# NutX_Keyboard_PCB_ANSI104.net
KiCad netlist of a schematic drawn in Altium Designer
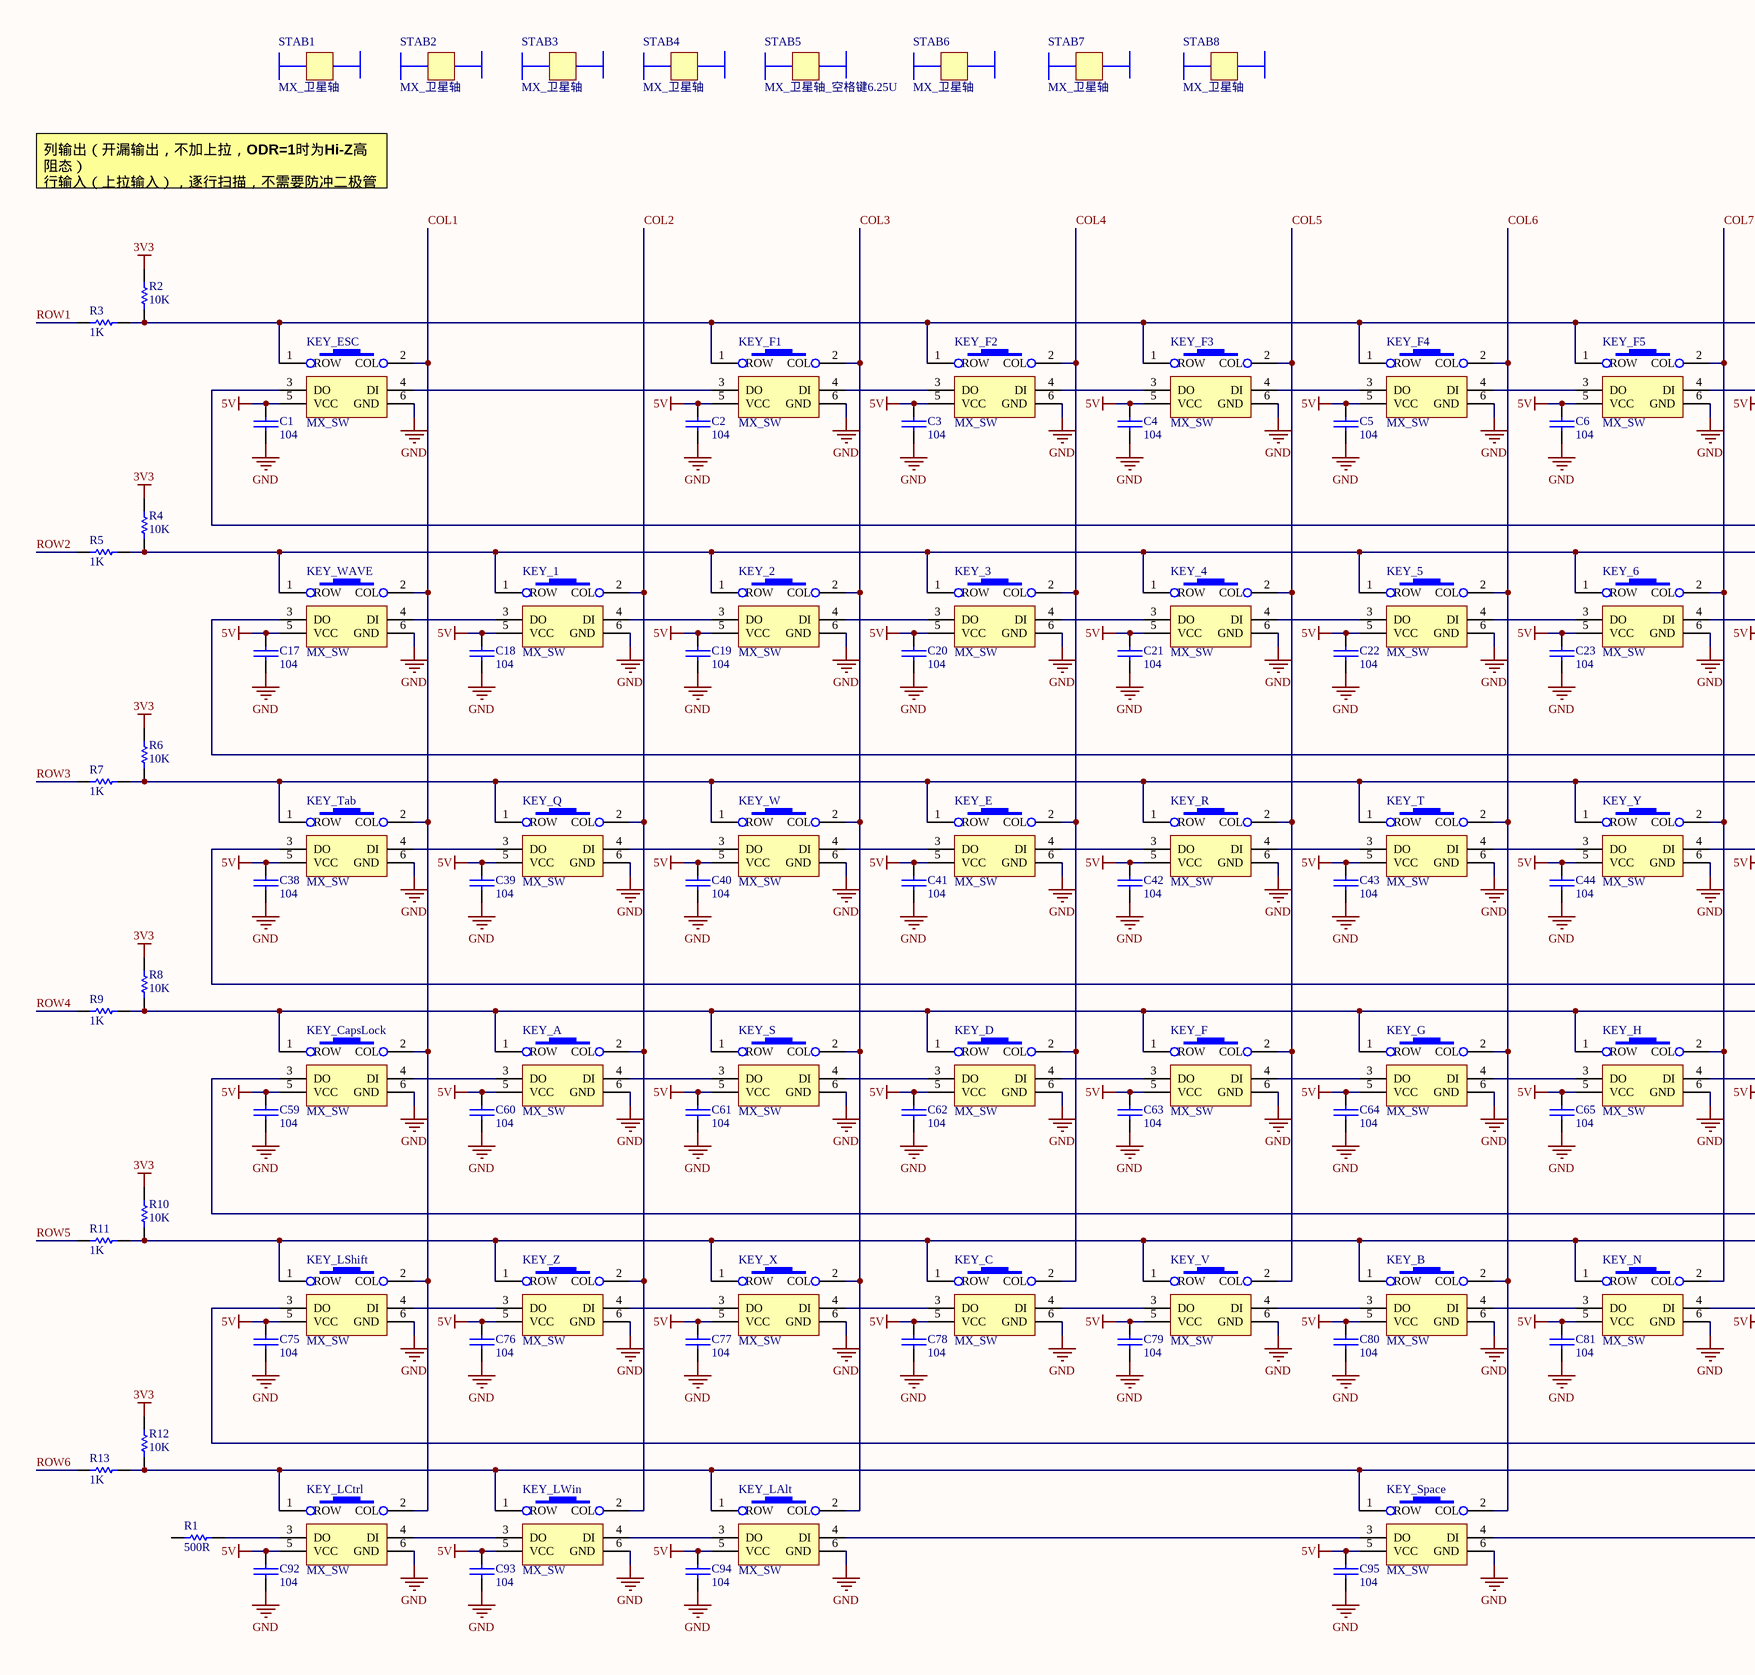
[diagram p0: NutX_Keyboard_PCB_ANSI104.SchDoc, left]
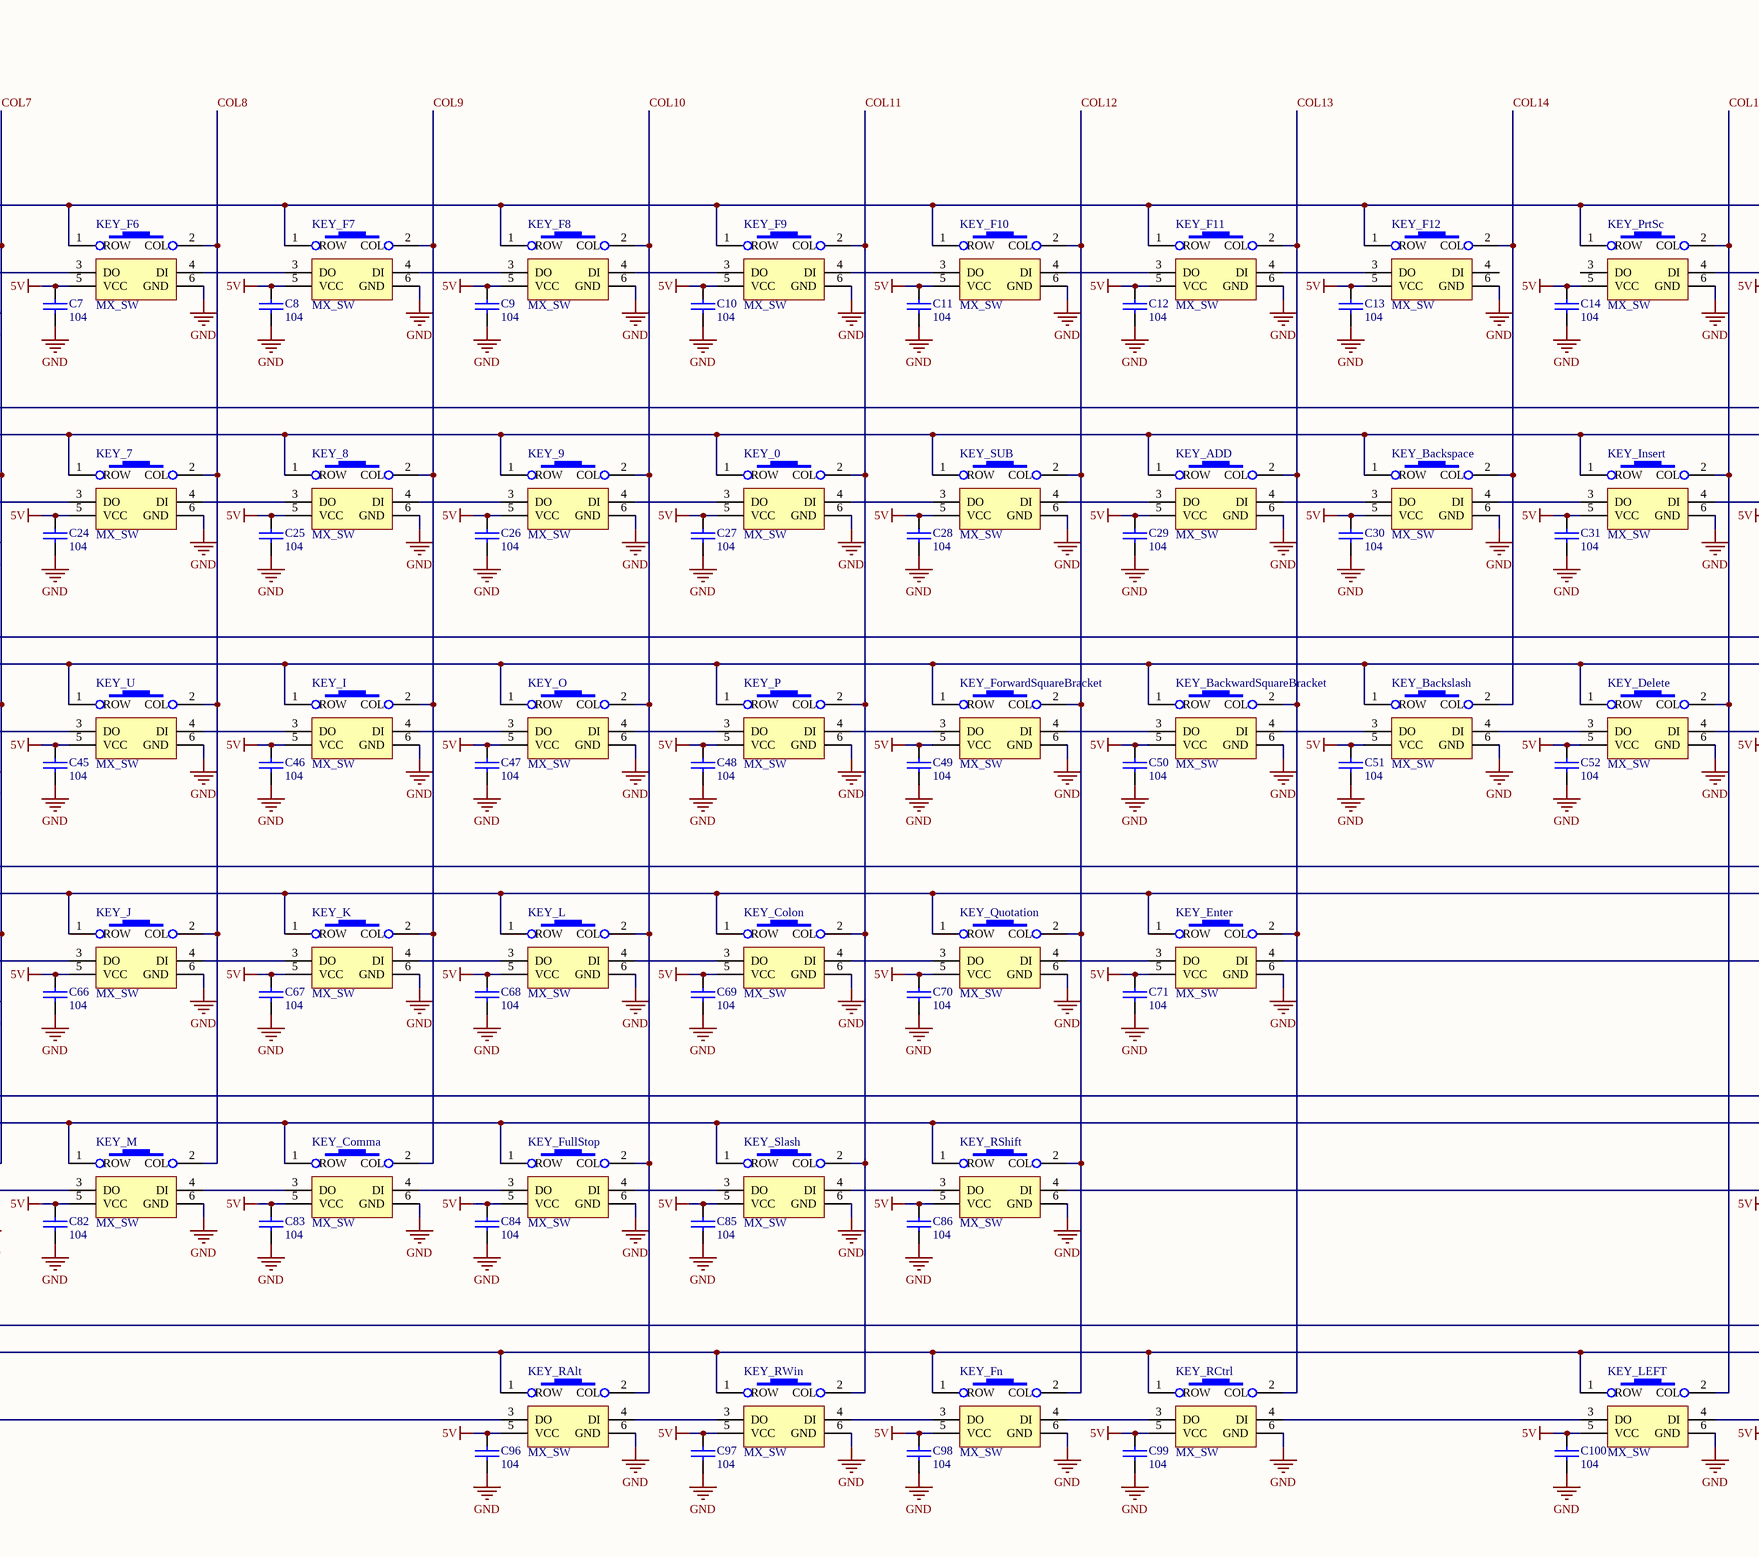
[diagram p1: NutX_Keyboard_PCB_ANSI104.SchDoc, middle]
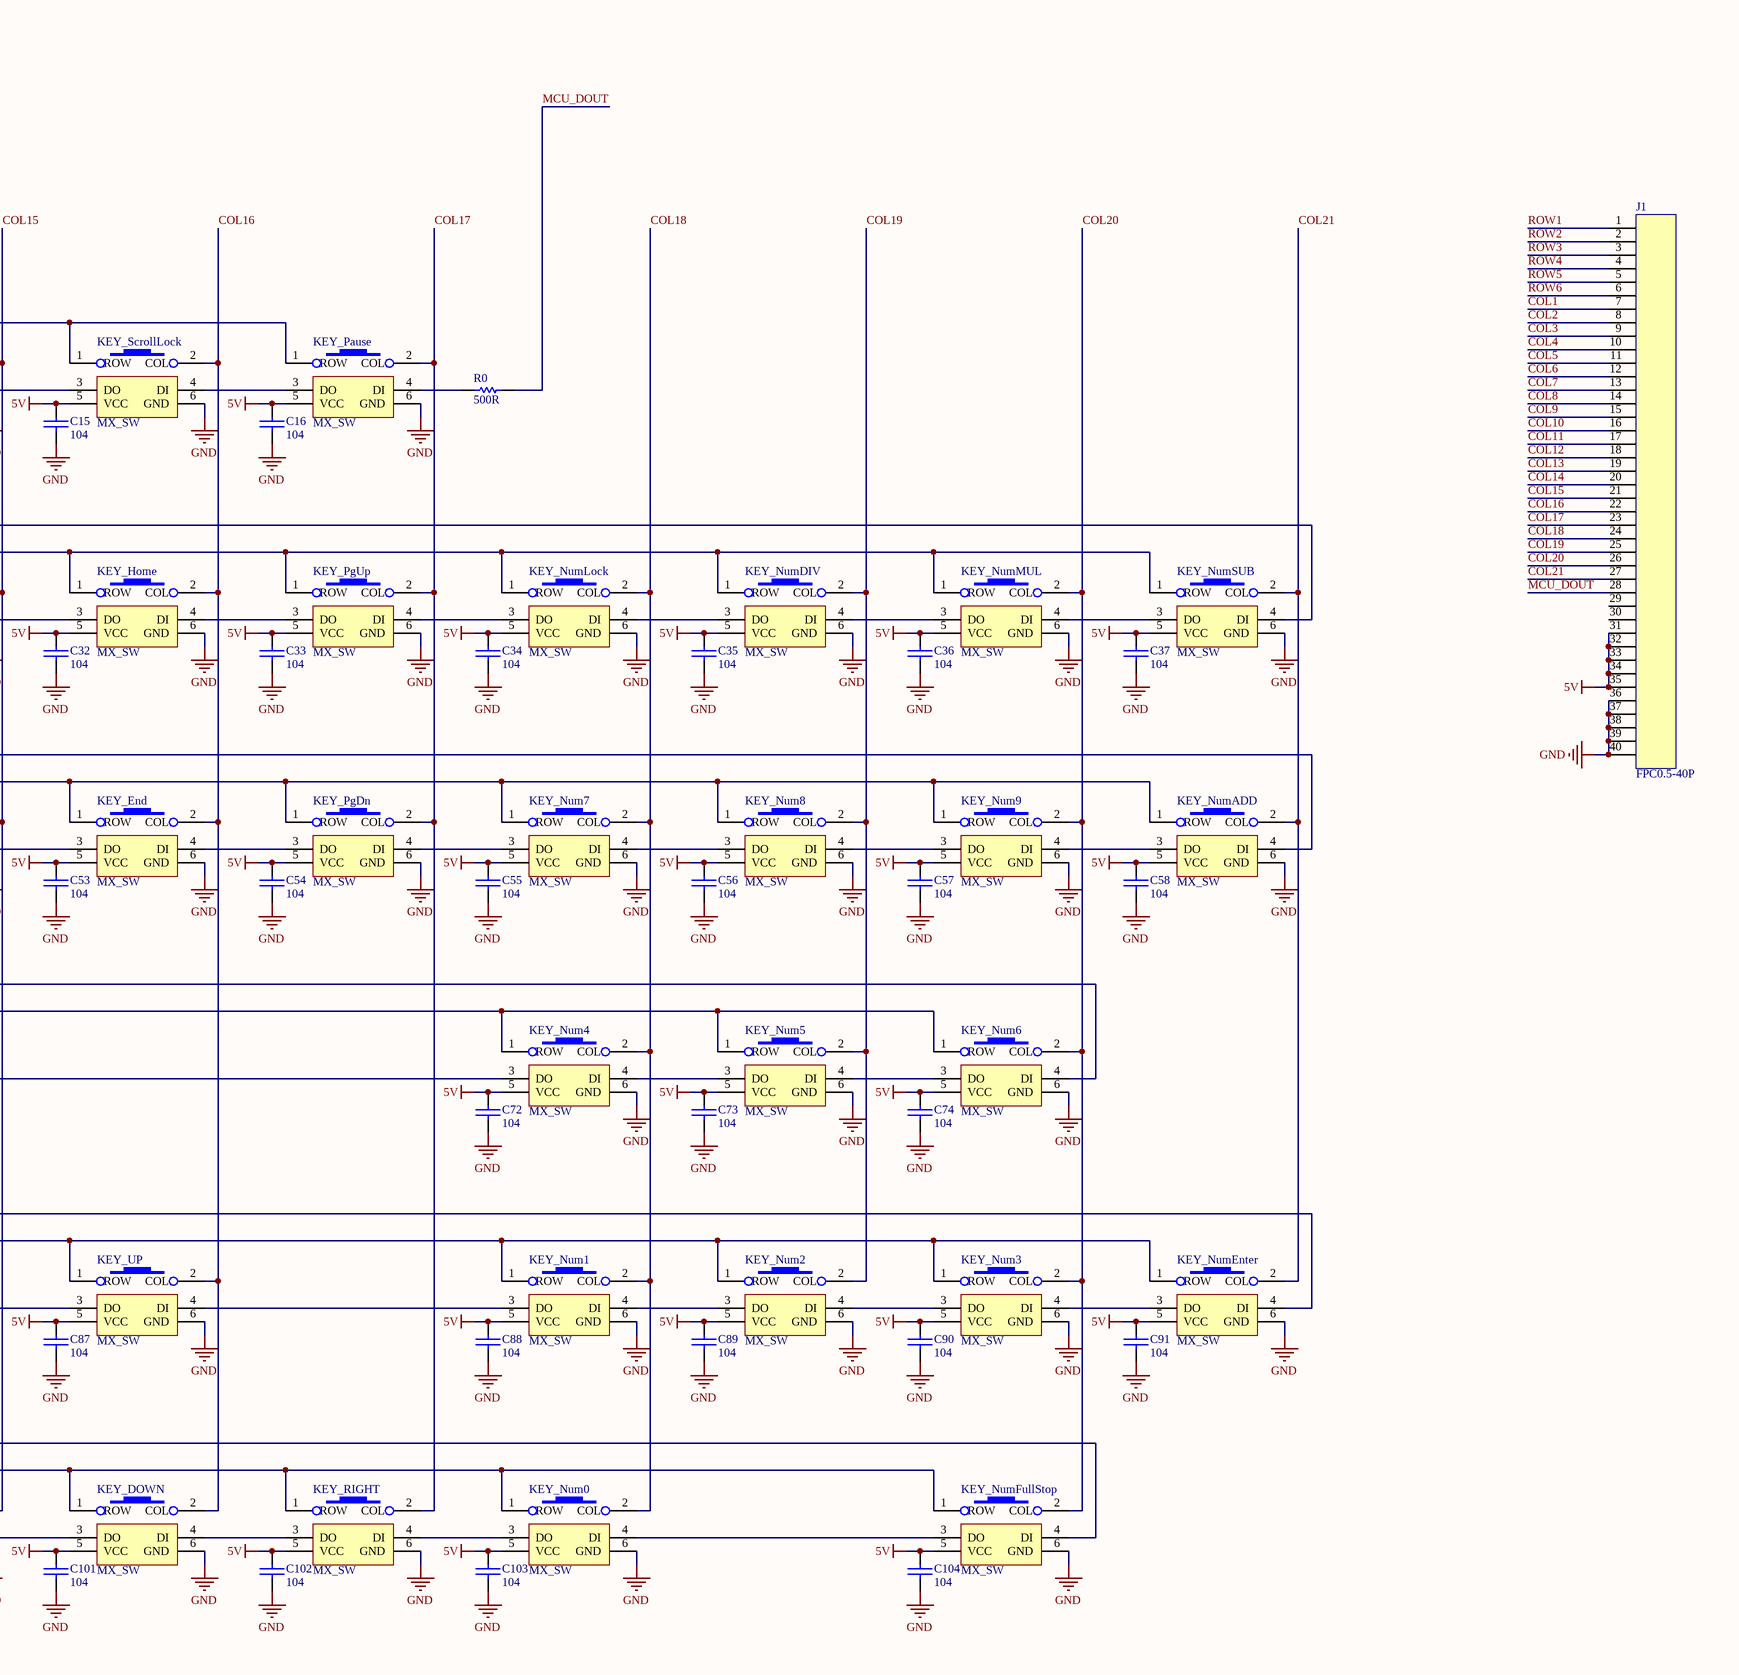
[diagram p2: NutX_Keyboard_PCB_ANSI104.SchDoc, right]

(export (version "E")
  (design (tool "Eeschema 10.0.6"))
  (components
    (comp (ref "C1")
      (value "104")
      (footprint "0603C")
      (description "无极性电容")
      (libsource (lib "电容") (part "CAP"))
    )
    (comp (ref "C2")
      (value "104")
      (footprint "0603C")
      (description "无极性电容")
      (libsource (lib "电容") (part "CAP"))
    )
    (comp (ref "C3")
      (value "104")
      (footprint "0603C")
      (description "无极性电容")
      (libsource (lib "电容") (part "CAP"))
    )
    (comp (ref "C4")
      (value "104")
      (footprint "0603C")
      (description "无极性电容")
      (libsource (lib "电容") (part "CAP"))
    )
    (comp (ref "C5")
      (value "104")
      (footprint "0603C")
      (description "无极性电容")
      (libsource (lib "电容") (part "CAP"))
    )
    (comp (ref "C6")
      (value "104")
      (footprint "0603C")
      (description "无极性电容")
      (libsource (lib "电容") (part "CAP"))
    )
    (comp (ref "C7")
      (value "104")
      (footprint "0603C")
      (description "无极性电容")
      (libsource (lib "电容") (part "CAP"))
    )
    (comp (ref "C8")
      (value "104")
      (footprint "0603C")
      (description "无极性电容")
      (libsource (lib "电容") (part "CAP"))
    )
    (comp (ref "C9")
      (value "104")
      (footprint "0603C")
      (description "无极性电容")
      (libsource (lib "电容") (part "CAP"))
    )
    (comp (ref "C10")
      (value "104")
      (footprint "0603C")
      (description "无极性电容")
      (libsource (lib "电容") (part "CAP"))
    )
    (comp (ref "C11")
      (value "104")
      (footprint "0603C")
      (description "无极性电容")
      (libsource (lib "电容") (part "CAP"))
    )
    (comp (ref "C12")
      (value "104")
      (footprint "0603C")
      (description "无极性电容")
      (libsource (lib "电容") (part "CAP"))
    )
    (comp (ref "C13")
      (value "104")
      (footprint "0603C")
      (description "无极性电容")
      (libsource (lib "电容") (part "CAP"))
    )
    (comp (ref "C14")
      (value "104")
      (footprint "0603C")
      (description "无极性电容")
      (libsource (lib "电容") (part "CAP"))
    )
    (comp (ref "C15")
      (value "104")
      (footprint "0603C")
      (description "无极性电容")
      (libsource (lib "电容") (part "CAP"))
    )
    (comp (ref "C16")
      (value "104")
      (footprint "0603C")
      (description "无极性电容")
      (libsource (lib "电容") (part "CAP"))
    )
    (comp (ref "C17")
      (value "104")
      (footprint "0603C")
      (description "无极性电容")
      (libsource (lib "电容") (part "CAP"))
    )
    (comp (ref "C18")
      (value "104")
      (footprint "0603C")
      (description "无极性电容")
      (libsource (lib "电容") (part "CAP"))
    )
    (comp (ref "C19")
      (value "104")
      (footprint "0603C")
      (description "无极性电容")
      (libsource (lib "电容") (part "CAP"))
    )
    (comp (ref "C20")
      (value "104")
      (footprint "0603C")
      (description "无极性电容")
      (libsource (lib "电容") (part "CAP"))
    )
    (comp (ref "C21")
      (value "104")
      (footprint "0603C")
      (description "无极性电容")
      (libsource (lib "电容") (part "CAP"))
    )
    (comp (ref "C22")
      (value "104")
      (footprint "0603C")
      (description "无极性电容")
      (libsource (lib "电容") (part "CAP"))
    )
    (comp (ref "C23")
      (value "104")
      (footprint "0603C")
      (description "无极性电容")
      (libsource (lib "电容") (part "CAP"))
    )
    (comp (ref "C24")
      (value "104")
      (footprint "0603C")
      (description "无极性电容")
      (libsource (lib "电容") (part "CAP"))
    )
    (comp (ref "C25")
      (value "104")
      (footprint "0603C")
      (description "无极性电容")
      (libsource (lib "电容") (part "CAP"))
    )
    (comp (ref "C26")
      (value "104")
      (footprint "0603C")
      (description "无极性电容")
      (libsource (lib "电容") (part "CAP"))
    )
    (comp (ref "C27")
      (value "104")
      (footprint "0603C")
      (description "无极性电容")
      (libsource (lib "电容") (part "CAP"))
    )
    (comp (ref "C28")
      (value "104")
      (footprint "0603C")
      (description "无极性电容")
      (libsource (lib "电容") (part "CAP"))
    )
    (comp (ref "C29")
      (value "104")
      (footprint "0603C")
      (description "无极性电容")
      (libsource (lib "电容") (part "CAP"))
    )
    (comp (ref "C30")
      (value "104")
      (footprint "0603C")
      (description "无极性电容")
      (libsource (lib "电容") (part "CAP"))
    )
    (comp (ref "C31")
      (value "104")
      (footprint "0603C")
      (description "无极性电容")
      (libsource (lib "电容") (part "CAP"))
    )
    (comp (ref "C32")
      (value "104")
      (footprint "0603C")
      (description "无极性电容")
      (libsource (lib "电容") (part "CAP"))
    )
    (comp (ref "C33")
      (value "104")
      (footprint "0603C")
      (description "无极性电容")
      (libsource (lib "电容") (part "CAP"))
    )
    (comp (ref "C34")
      (value "104")
      (footprint "0603C")
      (description "无极性电容")
      (libsource (lib "电容") (part "CAP"))
    )
    (comp (ref "C35")
      (value "104")
      (footprint "0603C")
      (description "无极性电容")
      (libsource (lib "电容") (part "CAP"))
    )
    (comp (ref "C36")
      (value "104")
      (footprint "0603C")
      (description "无极性电容")
      (libsource (lib "电容") (part "CAP"))
    )
    (comp (ref "C37")
      (value "104")
      (footprint "0603C")
      (description "无极性电容")
      (libsource (lib "电容") (part "CAP"))
    )
    (comp (ref "C38")
      (value "104")
      (footprint "0603C")
      (description "无极性电容")
      (libsource (lib "电容") (part "CAP"))
    )
    (comp (ref "C39")
      (value "104")
      (footprint "0603C")
      (description "无极性电容")
      (libsource (lib "电容") (part "CAP"))
    )
    (comp (ref "C40")
      (value "104")
      (footprint "0603C")
      (description "无极性电容")
      (libsource (lib "电容") (part "CAP"))
    )
    (comp (ref "C41")
      (value "104")
      (footprint "0603C")
      (description "无极性电容")
      (libsource (lib "电容") (part "CAP"))
    )
    (comp (ref "C42")
      (value "104")
      (footprint "0603C")
      (description "无极性电容")
      (libsource (lib "电容") (part "CAP"))
    )
    (comp (ref "C43")
      (value "104")
      (footprint "0603C")
      (description "无极性电容")
      (libsource (lib "电容") (part "CAP"))
    )
    (comp (ref "C44")
      (value "104")
      (footprint "0603C")
      (description "无极性电容")
      (libsource (lib "电容") (part "CAP"))
    )
    (comp (ref "C45")
      (value "104")
      (footprint "0603C")
      (description "无极性电容")
      (libsource (lib "电容") (part "CAP"))
    )
    (comp (ref "C46")
      (value "104")
      (footprint "0603C")
      (description "无极性电容")
      (libsource (lib "电容") (part "CAP"))
    )
    (comp (ref "C47")
      (value "104")
      (footprint "0603C")
      (description "无极性电容")
      (libsource (lib "电容") (part "CAP"))
    )
    (comp (ref "C48")
      (value "104")
      (footprint "0603C")
      (description "无极性电容")
      (libsource (lib "电容") (part "CAP"))
    )
    (comp (ref "C49")
      (value "104")
      (footprint "0603C")
      (description "无极性电容")
      (libsource (lib "电容") (part "CAP"))
    )
    (comp (ref "C50")
      (value "104")
      (footprint "0603C")
      (description "无极性电容")
      (libsource (lib "电容") (part "CAP"))
    )
    (comp (ref "C51")
      (value "104")
      (footprint "0603C")
      (description "无极性电容")
      (libsource (lib "电容") (part "CAP"))
    )
    (comp (ref "C52")
      (value "104")
      (footprint "0603C")
      (description "无极性电容")
      (libsource (lib "电容") (part "CAP"))
    )
    (comp (ref "C53")
      (value "104")
      (footprint "0603C")
      (description "无极性电容")
      (libsource (lib "电容") (part "CAP"))
    )
    (comp (ref "C54")
      (value "104")
      (footprint "0603C")
      (description "无极性电容")
      (libsource (lib "电容") (part "CAP"))
    )
    (comp (ref "C55")
      (value "104")
      (footprint "0603C")
      (description "无极性电容")
      (libsource (lib "电容") (part "CAP"))
    )
    (comp (ref "C56")
      (value "104")
      (footprint "0603C")
      (description "无极性电容")
      (libsource (lib "电容") (part "CAP"))
    )
    (comp (ref "C57")
      (value "104")
      (footprint "0603C")
      (description "无极性电容")
      (libsource (lib "电容") (part "CAP"))
    )
    (comp (ref "C58")
      (value "104")
      (footprint "0603C")
      (description "无极性电容")
      (libsource (lib "电容") (part "CAP"))
    )
    (comp (ref "C59")
      (value "104")
      (footprint "0603C")
      (description "无极性电容")
      (libsource (lib "电容") (part "CAP"))
    )
    (comp (ref "C60")
      (value "104")
      (footprint "0603C")
      (description "无极性电容")
      (libsource (lib "电容") (part "CAP"))
    )
    (comp (ref "C61")
      (value "104")
      (footprint "0603C")
      (description "无极性电容")
      (libsource (lib "电容") (part "CAP"))
    )
    (comp (ref "C62")
      (value "104")
      (footprint "0603C")
      (description "无极性电容")
      (libsource (lib "电容") (part "CAP"))
    )
    (comp (ref "C63")
      (value "104")
      (footprint "0603C")
      (description "无极性电容")
      (libsource (lib "电容") (part "CAP"))
    )
    (comp (ref "C64")
      (value "104")
      (footprint "0603C")
      (description "无极性电容")
      (libsource (lib "电容") (part "CAP"))
    )
    (comp (ref "C65")
      (value "104")
      (footprint "0603C")
      (description "无极性电容")
      (libsource (lib "电容") (part "CAP"))
    )
    (comp (ref "C66")
      (value "104")
      (footprint "0603C")
      (description "无极性电容")
      (libsource (lib "电容") (part "CAP"))
    )
    (comp (ref "C67")
      (value "104")
      (footprint "0603C")
      (description "无极性电容")
      (libsource (lib "电容") (part "CAP"))
    )
    (comp (ref "C68")
      (value "104")
      (footprint "0603C")
      (description "无极性电容")
      (libsource (lib "电容") (part "CAP"))
    )
    (comp (ref "C69")
      (value "104")
      (footprint "0603C")
      (description "无极性电容")
      (libsource (lib "电容") (part "CAP"))
    )
    (comp (ref "C70")
      (value "104")
      (footprint "0603C")
      (description "无极性电容")
      (libsource (lib "电容") (part "CAP"))
    )
    (comp (ref "C71")
      (value "104")
      (footprint "0603C")
      (description "无极性电容")
      (libsource (lib "电容") (part "CAP"))
    )
    (comp (ref "C72")
      (value "104")
      (footprint "0603C")
      (description "无极性电容")
      (libsource (lib "电容") (part "CAP"))
    )
    (comp (ref "C73")
      (value "104")
      (footprint "0603C")
      (description "无极性电容")
      (libsource (lib "电容") (part "CAP"))
    )
    (comp (ref "C74")
      (value "104")
      (footprint "0603C")
      (description "无极性电容")
      (libsource (lib "电容") (part "CAP"))
    )
    (comp (ref "C75")
      (value "104")
      (footprint "0603C")
      (description "无极性电容")
      (libsource (lib "电容") (part "CAP"))
    )
    (comp (ref "C76")
      (value "104")
      (footprint "0603C")
      (description "无极性电容")
      (libsource (lib "电容") (part "CAP"))
    )
    (comp (ref "C77")
      (value "104")
      (footprint "0603C")
      (description "无极性电容")
      (libsource (lib "电容") (part "CAP"))
    )
    (comp (ref "C78")
      (value "104")
      (footprint "0603C")
      (description "无极性电容")
      (libsource (lib "电容") (part "CAP"))
    )
    (comp (ref "C79")
      (value "104")
      (footprint "0603C")
      (description "无极性电容")
      (libsource (lib "电容") (part "CAP"))
    )
    (comp (ref "C80")
      (value "104")
      (footprint "0603C")
      (description "无极性电容")
      (libsource (lib "电容") (part "CAP"))
    )
    (comp (ref "C81")
      (value "104")
      (footprint "0603C")
      (description "无极性电容")
      (libsource (lib "电容") (part "CAP"))
    )
    (comp (ref "C82")
      (value "104")
      (footprint "0603C")
      (description "无极性电容")
      (libsource (lib "电容") (part "CAP"))
    )
    (comp (ref "C83")
      (value "104")
      (footprint "0603C")
      (description "无极性电容")
      (libsource (lib "电容") (part "CAP"))
    )
    (comp (ref "C84")
      (value "104")
      (footprint "0603C")
      (description "无极性电容")
      (libsource (lib "电容") (part "CAP"))
    )
    (comp (ref "C85")
      (value "104")
      (footprint "0603C")
      (description "无极性电容")
      (libsource (lib "电容") (part "CAP"))
    )
    (comp (ref "C86")
      (value "104")
      (footprint "0603C")
      (description "无极性电容")
      (libsource (lib "电容") (part "CAP"))
    )
    (comp (ref "C87")
      (value "104")
      (footprint "0603C")
      (description "无极性电容")
      (libsource (lib "电容") (part "CAP"))
    )
    (comp (ref "C88")
      (value "104")
      (footprint "0603C")
      (description "无极性电容")
      (libsource (lib "电容") (part "CAP"))
    )
    (comp (ref "C89")
      (value "104")
      (footprint "0603C")
      (description "无极性电容")
      (libsource (lib "电容") (part "CAP"))
    )
    (comp (ref "C90")
      (value "104")
      (footprint "0603C")
      (description "无极性电容")
      (libsource (lib "电容") (part "CAP"))
    )
    (comp (ref "C91")
      (value "104")
      (footprint "0603C")
      (description "无极性电容")
      (libsource (lib "电容") (part "CAP"))
    )
    (comp (ref "C92")
      (value "104")
      (footprint "0603C")
      (description "无极性电容")
      (libsource (lib "电容") (part "CAP"))
    )
    (comp (ref "C93")
      (value "104")
      (footprint "0603C")
      (description "无极性电容")
      (libsource (lib "电容") (part "CAP"))
    )
    (comp (ref "C94")
      (value "104")
      (footprint "0603C")
      (description "无极性电容")
      (libsource (lib "电容") (part "CAP"))
    )
    (comp (ref "C95")
      (value "104")
      (footprint "0603C")
      (description "无极性电容")
      (libsource (lib "电容") (part "CAP"))
    )
    (comp (ref "C96")
      (value "104")
      (footprint "0603C")
      (description "无极性电容")
      (libsource (lib "电容") (part "CAP"))
    )
    (comp (ref "C97")
      (value "104")
      (footprint "0603C")
      (description "无极性电容")
      (libsource (lib "电容") (part "CAP"))
    )
    (comp (ref "C98")
      (value "104")
      (footprint "0603C")
      (description "无极性电容")
      (libsource (lib "电容") (part "CAP"))
    )
    (comp (ref "C99")
      (value "104")
      (footprint "0603C")
      (description "无极性电容")
      (libsource (lib "电容") (part "CAP"))
    )
    (comp (ref "C100")
      (value "104")
      (footprint "0603C")
      (description "无极性电容")
      (libsource (lib "电容") (part "CAP"))
    )
    (comp (ref "C101")
      (value "104")
      (footprint "0603C")
      (description "无极性电容")
      (libsource (lib "电容") (part "CAP"))
    )
    (comp (ref "C102")
      (value "104")
      (footprint "0603C")
      (description "无极性电容")
      (libsource (lib "电容") (part "CAP"))
    )
    (comp (ref "C103")
      (value "104")
      (footprint "0603C")
      (description "无极性电容")
      (libsource (lib "电容") (part "CAP"))
    )
    (comp (ref "C104")
      (value "104")
      (footprint "0603C")
      (description "无极性电容")
      (libsource (lib "电容") (part "CAP"))
    )
    (comp (ref "J1")
      (value "FPC0.5-40P")
      (footprint "FPC0.5-40P")
      (description "贴片")
      (libsource (lib "FPC") (part "FPC0.5-40P"))
    )
    (comp (ref "KEY_0")
      (value "MX_SW")
      (footprint "MX_Normal_1U")
      (libsource (lib "凯华热插拔-SK6812-3528反贴") (part "MX_SW"))
    )
    (comp (ref "KEY_1")
      (value "MX_SW")
      (footprint "MX_Normal_1U")
      (libsource (lib "凯华热插拔-SK6812-3528反贴") (part "MX_SW"))
    )
    (comp (ref "KEY_2")
      (value "MX_SW")
      (footprint "MX_Normal_1U")
      (libsource (lib "凯华热插拔-SK6812-3528反贴") (part "MX_SW"))
    )
    (comp (ref "KEY_3")
      (value "MX_SW")
      (footprint "MX_Normal_1U")
      (libsource (lib "凯华热插拔-SK6812-3528反贴") (part "MX_SW"))
    )
    (comp (ref "KEY_4")
      (value "MX_SW")
      (footprint "MX_Normal_1U")
      (libsource (lib "凯华热插拔-SK6812-3528反贴") (part "MX_SW"))
    )
    (comp (ref "KEY_5")
      (value "MX_SW")
      (footprint "MX_Normal_1U")
      (libsource (lib "凯华热插拔-SK6812-3528反贴") (part "MX_SW"))
    )
    (comp (ref "KEY_6")
      (value "MX_SW")
      (footprint "MX_Normal_1U")
      (libsource (lib "凯华热插拔-SK6812-3528反贴") (part "MX_SW"))
    )
    (comp (ref "KEY_7")
      (value "MX_SW")
      (footprint "MX_Normal_1U")
      (libsource (lib "凯华热插拔-SK6812-3528反贴") (part "MX_SW"))
    )
    (comp (ref "KEY_8")
      (value "MX_SW")
      (footprint "MX_Normal_1U")
      (libsource (lib "凯华热插拔-SK6812-3528反贴") (part "MX_SW"))
    )
    (comp (ref "KEY_9")
      (value "MX_SW")
      (footprint "MX_Normal_1U")
      (libsource (lib "凯华热插拔-SK6812-3528反贴") (part "MX_SW"))
    )
    (comp (ref "KEY_A")
      (value "MX_SW")
      (footprint "MX_Normal_1U")
      (libsource (lib "凯华热插拔-SK6812-3528反贴") (part "MX_SW"))
    )
    (comp (ref "KEY_ADD")
      (value "MX_SW")
      (footprint "MX_Normal_1U")
      (libsource (lib "凯华热插拔-SK6812-3528反贴") (part "MX_SW"))
    )
    (comp (ref "KEY_B")
      (value "MX_SW")
      (footprint "MX_Normal_1U")
      (libsource (lib "凯华热插拔-SK6812-3528反贴") (part "MX_SW"))
    )
    (comp (ref "KEY_Backslash")
      (value "MX_SW")
      (footprint "MX_Tab_1.5U")
      (libsource (lib "凯华热插拔-SK6812-3528反贴") (part "MX_SW"))
    )
    (comp (ref "KEY_Backspace")
      (value "MX_SW")
      (footprint "MX_Backspace_2U")
      (libsource (lib "凯华热插拔-SK6812-3528反贴") (part "MX_SW"))
    )
    (comp (ref "KEY_BackwardSquareBracket")
      (value "MX_SW")
      (footprint "MX_Normal_1U")
      (libsource (lib "凯华热插拔-SK6812-3528反贴") (part "MX_SW"))
    )
    (comp (ref "KEY_C")
      (value "MX_SW")
      (footprint "MX_Normal_1U")
      (libsource (lib "凯华热插拔-SK6812-3528反贴") (part "MX_SW"))
    )
    (comp (ref "KEY_CapsLock")
      (value "MX_SW")
      (footprint "MX_CapsLock_1.75U")
      (libsource (lib "凯华热插拔-SK6812-3528反贴") (part "MX_SW"))
    )
    (comp (ref "KEY_Colon")
      (value "MX_SW")
      (footprint "MX_Normal_1U")
      (libsource (lib "凯华热插拔-SK6812-3528反贴") (part "MX_SW"))
    )
    (comp (ref "KEY_Comma")
      (value "MX_SW")
      (footprint "MX_Normal_1U")
      (libsource (lib "凯华热插拔-SK6812-3528反贴") (part "MX_SW"))
    )
    (comp (ref "KEY_D")
      (value "MX_SW")
      (footprint "MX_Normal_1U")
      (libsource (lib "凯华热插拔-SK6812-3528反贴") (part "MX_SW"))
    )
    (comp (ref "KEY_Delete")
      (value "MX_SW")
      (footprint "MX_Normal_1U")
      (libsource (lib "凯华热插拔-SK6812-3528反贴") (part "MX_SW"))
    )
    (comp (ref "KEY_DOWN")
      (value "MX_SW")
      (footprint "MX_Normal_1U")
      (libsource (lib "凯华热插拔-SK6812-3528反贴") (part "MX_SW"))
    )
    (comp (ref "KEY_E")
      (value "MX_SW")
      (footprint "MX_Normal_1U")
      (libsource (lib "凯华热插拔-SK6812-3528反贴") (part "MX_SW"))
    )
    (comp (ref "KEY_End")
      (value "MX_SW")
      (footprint "MX_Normal_1U")
      (libsource (lib "凯华热插拔-SK6812-3528反贴") (part "MX_SW"))
    )
    (comp (ref "KEY_Enter")
      (value "MX_SW")
      (footprint "MX_LeftShift_Enter_2.25U")
      (libsource (lib "凯华热插拔-SK6812-3528反贴") (part "MX_SW"))
    )
    (comp (ref "KEY_ESC")
      (value "MX_SW")
      (footprint "MX_Normal_1U")
      (libsource (lib "凯华热插拔-SK6812-3528反贴") (part "MX_SW"))
    )
    (comp (ref "KEY_F")
      (value "MX_SW")
      (footprint "MX_Normal_1U")
      (libsource (lib "凯华热插拔-SK6812-3528反贴") (part "MX_SW"))
    )
    (comp (ref "KEY_F1")
      (value "MX_SW")
      (footprint "MX_Normal_1U")
      (libsource (lib "凯华热插拔-SK6812-3528反贴") (part "MX_SW"))
    )
    (comp (ref "KEY_F2")
      (value "MX_SW")
      (footprint "MX_Normal_1U")
      (libsource (lib "凯华热插拔-SK6812-3528反贴") (part "MX_SW"))
    )
    (comp (ref "KEY_F3")
      (value "MX_SW")
      (footprint "MX_Normal_1U")
      (libsource (lib "凯华热插拔-SK6812-3528反贴") (part "MX_SW"))
    )
    (comp (ref "KEY_F4")
      (value "MX_SW")
      (footprint "MX_Normal_1U")
      (libsource (lib "凯华热插拔-SK6812-3528反贴") (part "MX_SW"))
    )
    (comp (ref "KEY_F5")
      (value "MX_SW")
      (footprint "MX_Normal_1U")
      (libsource (lib "凯华热插拔-SK6812-3528反贴") (part "MX_SW"))
    )
    (comp (ref "KEY_F6")
      (value "MX_SW")
      (footprint "MX_Normal_1U")
      (libsource (lib "凯华热插拔-SK6812-3528反贴") (part "MX_SW"))
    )
    (comp (ref "KEY_F7")
      (value "MX_SW")
      (footprint "MX_Normal_1U")
      (libsource (lib "凯华热插拔-SK6812-3528反贴") (part "MX_SW"))
    )
    (comp (ref "KEY_F8")
      (value "MX_SW")
      (footprint "MX_Normal_1U")
      (libsource (lib "凯华热插拔-SK6812-3528反贴") (part "MX_SW"))
    )
    (comp (ref "KEY_F9")
      (value "MX_SW")
      (footprint "MX_Normal_1U")
      (libsource (lib "凯华热插拔-SK6812-3528反贴") (part "MX_SW"))
    )
    (comp (ref "KEY_F10")
      (value "MX_SW")
      (footprint "MX_Normal_1U")
      (libsource (lib "凯华热插拔-SK6812-3528反贴") (part "MX_SW"))
    )
    (comp (ref "KEY_F11")
      (value "MX_SW")
      (footprint "MX_Normal_1U")
      (libsource (lib "凯华热插拔-SK6812-3528反贴") (part "MX_SW"))
    )
    (comp (ref "KEY_F12")
      (value "MX_SW")
      (footprint "MX_Normal_1U")
      (libsource (lib "凯华热插拔-SK6812-3528反贴") (part "MX_SW"))
    )
    (comp (ref "KEY_Fn")
      (value "MX_SW")
      (footprint "MX_Ctrl_Win_Alt_1.25U")
      (libsource (lib "凯华热插拔-SK6812-3528反贴") (part "MX_SW"))
    )
    (comp (ref "KEY_ForwardSquareBracket")
      (value "MX_SW")
      (footprint "MX_Normal_1U")
      (libsource (lib "凯华热插拔-SK6812-3528反贴") (part "MX_SW"))
    )
    (comp (ref "KEY_FullStop")
      (value "MX_SW")
      (footprint "MX_Normal_1U")
      (libsource (lib "凯华热插拔-SK6812-3528反贴") (part "MX_SW"))
    )
    (comp (ref "KEY_G")
      (value "MX_SW")
      (footprint "MX_Normal_1U")
      (libsource (lib "凯华热插拔-SK6812-3528反贴") (part "MX_SW"))
    )
    (comp (ref "KEY_H")
      (value "MX_SW")
      (footprint "MX_Normal_1U")
      (libsource (lib "凯华热插拔-SK6812-3528反贴") (part "MX_SW"))
    )
    (comp (ref "KEY_Home")
      (value "MX_SW")
      (footprint "MX_Normal_1U")
      (libsource (lib "凯华热插拔-SK6812-3528反贴") (part "MX_SW"))
    )
    (comp (ref "KEY_I")
      (value "MX_SW")
      (footprint "MX_Normal_1U")
      (libsource (lib "凯华热插拔-SK6812-3528反贴") (part "MX_SW"))
    )
    (comp (ref "KEY_Insert")
      (value "MX_SW")
      (footprint "MX_Normal_1U")
      (libsource (lib "凯华热插拔-SK6812-3528反贴") (part "MX_SW"))
    )
    (comp (ref "KEY_J")
      (value "MX_SW")
      (footprint "MX_Normal_1U")
      (libsource (lib "凯华热插拔-SK6812-3528反贴") (part "MX_SW"))
    )
    (comp (ref "KEY_K")
      (value "MX_SW")
      (footprint "MX_Normal_1U")
      (libsource (lib "凯华热插拔-SK6812-3528反贴") (part "MX_SW"))
    )
    (comp (ref "KEY_L")
      (value "MX_SW")
      (footprint "MX_Normal_1U")
      (libsource (lib "凯华热插拔-SK6812-3528反贴") (part "MX_SW"))
    )
    (comp (ref "KEY_LAlt")
      (value "MX_SW")
      (footprint "MX_Ctrl_Win_Alt_1.25U")
      (libsource (lib "凯华热插拔-SK6812-3528反贴") (part "MX_SW"))
    )
    (comp (ref "KEY_LCtrl")
      (value "MX_SW")
      (footprint "MX_Ctrl_Win_Alt_1.25U")
      (libsource (lib "凯华热插拔-SK6812-3528反贴") (part "MX_SW"))
    )
    (comp (ref "KEY_LEFT")
      (value "MX_SW")
      (footprint "MX_Normal_1U")
      (libsource (lib "凯华热插拔-SK6812-3528反贴") (part "MX_SW"))
    )
    (comp (ref "KEY_LShift")
      (value "MX_SW")
      (footprint "MX_LeftShift_Enter_2.25U")
      (libsource (lib "凯华热插拔-SK6812-3528反贴") (part "MX_SW"))
    )
    (comp (ref "KEY_LWin")
      (value "MX_SW")
      (footprint "MX_Ctrl_Win_Alt_1.25U")
      (libsource (lib "凯华热插拔-SK6812-3528反贴") (part "MX_SW"))
    )
    (comp (ref "KEY_M")
      (value "MX_SW")
      (footprint "MX_Normal_1U")
      (libsource (lib "凯华热插拔-SK6812-3528反贴") (part "MX_SW"))
    )
    (comp (ref "KEY_N")
      (value "MX_SW")
      (footprint "MX_Normal_1U")
      (libsource (lib "凯华热插拔-SK6812-3528反贴") (part "MX_SW"))
    )
    (comp (ref "KEY_Num0")
      (value "MX_SW")
      (footprint "MX_Backspace_2U")
      (libsource (lib "凯华热插拔-SK6812-3528反贴") (part "MX_SW"))
    )
    (comp (ref "KEY_Num1")
      (value "MX_SW")
      (footprint "MX_Normal_1U")
      (libsource (lib "凯华热插拔-SK6812-3528反贴") (part "MX_SW"))
    )
    (comp (ref "KEY_Num2")
      (value "MX_SW")
      (footprint "MX_Normal_1U")
      (libsource (lib "凯华热插拔-SK6812-3528反贴") (part "MX_SW"))
    )
    (comp (ref "KEY_Num3")
      (value "MX_SW")
      (footprint "MX_Normal_1U")
      (libsource (lib "凯华热插拔-SK6812-3528反贴") (part "MX_SW"))
    )
    (comp (ref "KEY_Num4")
      (value "MX_SW")
      (footprint "MX_Normal_1U")
      (libsource (lib "凯华热插拔-SK6812-3528反贴") (part "MX_SW"))
    )
    (comp (ref "KEY_Num5")
      (value "MX_SW")
      (footprint "MX_Normal_1U")
      (libsource (lib "凯华热插拔-SK6812-3528反贴") (part "MX_SW"))
    )
    (comp (ref "KEY_Num6")
      (value "MX_SW")
      (footprint "MX_Normal_1U")
      (libsource (lib "凯华热插拔-SK6812-3528反贴") (part "MX_SW"))
    )
    (comp (ref "KEY_Num7")
      (value "MX_SW")
      (footprint "MX_Normal_1U")
      (libsource (lib "凯华热插拔-SK6812-3528反贴") (part "MX_SW"))
    )
    (comp (ref "KEY_Num8")
      (value "MX_SW")
      (footprint "MX_Normal_1U")
      (libsource (lib "凯华热插拔-SK6812-3528反贴") (part "MX_SW"))
    )
    (comp (ref "KEY_Num9")
      (value "MX_SW")
      (footprint "MX_Normal_1U")
      (libsource (lib "凯华热插拔-SK6812-3528反贴") (part "MX_SW"))
    )
    (comp (ref "KEY_NumADD")
      (value "MX_SW")
      (footprint "MX_Backspace_2U")
      (libsource (lib "凯华热插拔-SK6812-3528反贴") (part "MX_SW"))
    )
    (comp (ref "KEY_NumDIV")
      (value "MX_SW")
      (footprint "MX_Normal_1U")
      (libsource (lib "凯华热插拔-SK6812-3528反贴") (part "MX_SW"))
    )
    (comp (ref "KEY_NumEnter")
      (value "MX_SW")
      (footprint "MX_Backspace_2U")
      (libsource (lib "凯华热插拔-SK6812-3528反贴") (part "MX_SW"))
    )
    (comp (ref "KEY_NumFullStop")
      (value "MX_SW")
      (footprint "MX_Normal_1U")
      (libsource (lib "凯华热插拔-SK6812-3528反贴") (part "MX_SW"))
    )
    (comp (ref "KEY_NumLock")
      (value "MX_SW")
      (footprint "MX_Normal_1U")
      (libsource (lib "凯华热插拔-SK6812-3528反贴") (part "MX_SW"))
    )
    (comp (ref "KEY_NumMUL")
      (value "MX_SW")
      (footprint "MX_Normal_1U")
      (libsource (lib "凯华热插拔-SK6812-3528反贴") (part "MX_SW"))
    )
    (comp (ref "KEY_NumSUB")
      (value "MX_SW")
      (footprint "MX_Normal_1U")
      (libsource (lib "凯华热插拔-SK6812-3528反贴") (part "MX_SW"))
    )
    (comp (ref "KEY_O")
      (value "MX_SW")
      (footprint "MX_Normal_1U")
      (libsource (lib "凯华热插拔-SK6812-3528反贴") (part "MX_SW"))
    )
    (comp (ref "KEY_P")
      (value "MX_SW")
      (footprint "MX_Normal_1U")
      (libsource (lib "凯华热插拔-SK6812-3528反贴") (part "MX_SW"))
    )
    (comp (ref "KEY_Pause")
      (value "MX_SW")
      (footprint "MX_Normal_1U")
      (libsource (lib "凯华热插拔-SK6812-3528反贴") (part "MX_SW"))
    )
    (comp (ref "KEY_PgDn")
      (value "MX_SW")
      (footprint "MX_Normal_1U")
      (libsource (lib "凯华热插拔-SK6812-3528反贴") (part "MX_SW"))
    )
    (comp (ref "KEY_PgUp")
      (value "MX_SW")
      (footprint "MX_Normal_1U")
      (libsource (lib "凯华热插拔-SK6812-3528反贴") (part "MX_SW"))
    )
    (comp (ref "KEY_PrtSc")
      (value "MX_SW")
      (footprint "MX_Normal_1U")
      (libsource (lib "凯华热插拔-SK6812-3528反贴") (part "MX_SW"))
    )
    (comp (ref "KEY_Q")
      (value "MX_SW")
      (footprint "MX_Normal_1U")
      (libsource (lib "凯华热插拔-SK6812-3528反贴") (part "MX_SW"))
    )
    (comp (ref "KEY_Quotation")
      (value "MX_SW")
      (footprint "MX_Normal_1U")
      (libsource (lib "凯华热插拔-SK6812-3528反贴") (part "MX_SW"))
    )
    (comp (ref "KEY_R")
      (value "MX_SW")
      (footprint "MX_Normal_1U")
      (libsource (lib "凯华热插拔-SK6812-3528反贴") (part "MX_SW"))
    )
    (comp (ref "KEY_RAlt")
      (value "MX_SW")
      (footprint "MX_Ctrl_Win_Alt_1.25U")
      (libsource (lib "凯华热插拔-SK6812-3528反贴") (part "MX_SW"))
    )
    (comp (ref "KEY_RCtrl")
      (value "MX_SW")
      (footprint "MX_Ctrl_Win_Alt_1.25U")
      (libsource (lib "凯华热插拔-SK6812-3528反贴") (part "MX_SW"))
    )
    (comp (ref "KEY_RIGHT")
      (value "MX_SW")
      (footprint "MX_Normal_1U")
      (libsource (lib "凯华热插拔-SK6812-3528反贴") (part "MX_SW"))
    )
    (comp (ref "KEY_RShift")
      (value "MX_SW")
      (footprint "MX_RightShift_2.75U")
      (libsource (lib "凯华热插拔-SK6812-3528反贴") (part "MX_SW"))
    )
    (comp (ref "KEY_RWin")
      (value "MX_SW")
      (footprint "MX_Ctrl_Win_Alt_1.25U")
      (libsource (lib "凯华热插拔-SK6812-3528反贴") (part "MX_SW"))
    )
    (comp (ref "KEY_S")
      (value "MX_SW")
      (footprint "MX_Normal_1U")
      (libsource (lib "凯华热插拔-SK6812-3528反贴") (part "MX_SW"))
    )
    (comp (ref "KEY_ScrollLock")
      (value "MX_SW")
      (footprint "MX_Normal_1U")
      (libsource (lib "凯华热插拔-SK6812-3528反贴") (part "MX_SW"))
    )
    (comp (ref "KEY_Slash")
      (value "MX_SW")
      (footprint "MX_Normal_1U")
      (libsource (lib "凯华热插拔-SK6812-3528反贴") (part "MX_SW"))
    )
    (comp (ref "KEY_Space")
      (value "MX_SW")
      (footprint "MX_Space_6.25U")
      (libsource (lib "凯华热插拔-SK6812-3528反贴") (part "MX_SW"))
    )
    (comp (ref "KEY_SUB")
      (value "MX_SW")
      (footprint "MX_Normal_1U")
      (libsource (lib "凯华热插拔-SK6812-3528反贴") (part "MX_SW"))
    )
    (comp (ref "KEY_T")
      (value "MX_SW")
      (footprint "MX_Normal_1U")
      (libsource (lib "凯华热插拔-SK6812-3528反贴") (part "MX_SW"))
    )
    (comp (ref "KEY_Tab")
      (value "MX_SW")
      (footprint "MX_Tab_1.5U")
      (libsource (lib "凯华热插拔-SK6812-3528反贴") (part "MX_SW"))
    )
    (comp (ref "KEY_U")
      (value "MX_SW")
      (footprint "MX_Normal_1U")
      (libsource (lib "凯华热插拔-SK6812-3528反贴") (part "MX_SW"))
    )
    (comp (ref "KEY_UP")
      (value "MX_SW")
      (footprint "MX_Normal_1U")
      (libsource (lib "凯华热插拔-SK6812-3528反贴") (part "MX_SW"))
    )
    (comp (ref "KEY_V")
      (value "MX_SW")
      (footprint "MX_Normal_1U")
      (libsource (lib "凯华热插拔-SK6812-3528反贴") (part "MX_SW"))
    )
    (comp (ref "KEY_W")
      (value "MX_SW")
      (footprint "MX_Normal_1U")
      (libsource (lib "凯华热插拔-SK6812-3528反贴") (part "MX_SW"))
    )
    (comp (ref "KEY_WAVE")
      (value "MX_SW")
      (footprint "MX_Normal_1U")
      (libsource (lib "凯华热插拔-SK6812-3528反贴") (part "MX_SW"))
    )
    (comp (ref "KEY_X")
      (value "MX_SW")
      (footprint "MX_Normal_1U")
      (libsource (lib "凯华热插拔-SK6812-3528反贴") (part "MX_SW"))
    )
    (comp (ref "KEY_Y")
      (value "MX_SW")
      (footprint "MX_Normal_1U")
      (libsource (lib "凯华热插拔-SK6812-3528反贴") (part "MX_SW"))
    )
    (comp (ref "KEY_Z")
      (value "MX_SW")
      (footprint "MX_Normal_1U")
      (libsource (lib "凯华热插拔-SK6812-3528反贴") (part "MX_SW"))
    )
    (comp (ref "R0") (value "500R") (footprint "0603R") (libsource (lib "电阻") (part "RES")))
    (comp (ref "R1") (value "500R") (footprint "0603R") (libsource (lib "电阻") (part "RES")))
    (comp (ref "R2") (value "10K") (footprint "0603R") (libsource (lib "电阻") (part "RES")))
    (comp (ref "R3") (value "1K") (footprint "0603R") (libsource (lib "电阻") (part "RES")))
    (comp (ref "R4") (value "10K") (footprint "0603R") (libsource (lib "电阻") (part "RES")))
    (comp (ref "R5") (value "1K") (footprint "0603R") (libsource (lib "电阻") (part "RES")))
    (comp (ref "R6") (value "10K") (footprint "0603R") (libsource (lib "电阻") (part "RES")))
    (comp (ref "R7") (value "1K") (footprint "0603R") (libsource (lib "电阻") (part "RES")))
    (comp (ref "R8") (value "10K") (footprint "0603R") (libsource (lib "电阻") (part "RES")))
    (comp (ref "R9") (value "1K") (footprint "0603R") (libsource (lib "电阻") (part "RES")))
    (comp (ref "R10") (value "10K") (footprint "0603R") (libsource (lib "电阻") (part "RES")))
    (comp (ref "R11") (value "1K") (footprint "0603R") (libsource (lib "电阻") (part "RES")))
    (comp (ref "R12") (value "10K") (footprint "0603R") (libsource (lib "电阻") (part "RES")))
    (comp (ref "R13") (value "1K") (footprint "0603R") (libsource (lib "电阻") (part "RES")))
    (comp (ref "STAB1")
      (value "MX_卫星轴")
      (footprint "1X2")
      (description "Cherry MX Stabilizer 樱桃卫星轴")
      (libsource (lib "卫星轴") (part "MX_卫星轴"))
    )
    (comp (ref "STAB2")
      (value "MX_卫星轴")
      (footprint "1X2")
      (description "Cherry MX Stabilizer 樱桃卫星轴")
      (libsource (lib "卫星轴") (part "MX_卫星轴"))
    )
    (comp (ref "STAB3")
      (value "MX_卫星轴")
      (footprint "1X2")
      (description "Cherry MX Stabilizer 樱桃卫星轴")
      (libsource (lib "卫星轴") (part "MX_卫星轴"))
    )
    (comp (ref "STAB4")
      (value "MX_卫星轴")
      (footprint "1X2")
      (description "Cherry MX Stabilizer 樱桃卫星轴")
      (libsource (lib "卫星轴") (part "MX_卫星轴"))
    )
    (comp (ref "STAB5")
      (value "MX_卫星轴_空格键6.25U")
      (footprint "1x6.25")
      (description "Cherry MX Stabilizer 樱桃卫星轴")
      (libsource (lib "卫星轴") (part "MX_卫星轴"))
    )
    (comp (ref "STAB6")
      (value "MX_卫星轴")
      (footprint "1X2")
      (description "Cherry MX Stabilizer 樱桃卫星轴")
      (libsource (lib "卫星轴") (part "MX_卫星轴"))
    )
    (comp (ref "STAB7")
      (value "MX_卫星轴")
      (footprint "1X2")
      (description "Cherry MX Stabilizer 樱桃卫星轴")
      (libsource (lib "卫星轴") (part "MX_卫星轴"))
    )
    (comp (ref "STAB8")
      (value "MX_卫星轴")
      (footprint "1X2")
      (description "Cherry MX Stabilizer 樱桃卫星轴")
      (libsource (lib "卫星轴") (part "MX_卫星轴"))
    )
  )
  (nets
    (net (code "1") (name "/COL1") (class "Default")
      (node (ref "J1") (pin "7") (pinfunction "7_7") (pintype "passive"))
      (node (ref "KEY_CapsLock") (pin "2") (pinfunction "COL_2") (pintype "passive"))
      (node (ref "KEY_ESC") (pin "2") (pinfunction "COL_2") (pintype "passive"))
      (node (ref "KEY_LCtrl") (pin "2") (pinfunction "COL_2") (pintype "passive"))
      (node (ref "KEY_LShift") (pin "2") (pinfunction "COL_2") (pintype "passive"))
      (node (ref "KEY_Tab") (pin "2") (pinfunction "COL_2") (pintype "passive"))
      (node (ref "KEY_WAVE") (pin "2") (pinfunction "COL_2") (pintype "passive"))
    )
    (net (code "2") (name "/COL2") (class "Default")
      (node (ref "J1") (pin "8") (pinfunction "8_8") (pintype "passive"))
      (node (ref "KEY_1") (pin "2") (pinfunction "COL_2") (pintype "passive"))
      (node (ref "KEY_A") (pin "2") (pinfunction "COL_2") (pintype "passive"))
      (node (ref "KEY_LWin") (pin "2") (pinfunction "COL_2") (pintype "passive"))
      (node (ref "KEY_Q") (pin "2") (pinfunction "COL_2") (pintype "passive"))
      (node (ref "KEY_Z") (pin "2") (pinfunction "COL_2") (pintype "passive"))
    )
    (net (code "3") (name "/COL3") (class "Default")
      (node (ref "J1") (pin "9") (pinfunction "9_9") (pintype "passive"))
      (node (ref "KEY_2") (pin "2") (pinfunction "COL_2") (pintype "passive"))
      (node (ref "KEY_F1") (pin "2") (pinfunction "COL_2") (pintype "passive"))
      (node (ref "KEY_LAlt") (pin "2") (pinfunction "COL_2") (pintype "passive"))
      (node (ref "KEY_S") (pin "2") (pinfunction "COL_2") (pintype "passive"))
      (node (ref "KEY_W") (pin "2") (pinfunction "COL_2") (pintype "passive"))
      (node (ref "KEY_X") (pin "2") (pinfunction "COL_2") (pintype "passive"))
    )
    (net (code "4") (name "/COL4") (class "Default")
      (node (ref "J1") (pin "10") (pinfunction "10_10") (pintype "passive"))
      (node (ref "KEY_3") (pin "2") (pinfunction "COL_2") (pintype "passive"))
      (node (ref "KEY_C") (pin "2") (pinfunction "COL_2") (pintype "passive"))
      (node (ref "KEY_D") (pin "2") (pinfunction "COL_2") (pintype "passive"))
      (node (ref "KEY_E") (pin "2") (pinfunction "COL_2") (pintype "passive"))
      (node (ref "KEY_F2") (pin "2") (pinfunction "COL_2") (pintype "passive"))
    )
    (net (code "5") (name "/COL5") (class "Default")
      (node (ref "J1") (pin "11") (pinfunction "11_11") (pintype "passive"))
      (node (ref "KEY_4") (pin "2") (pinfunction "COL_2") (pintype "passive"))
      (node (ref "KEY_F") (pin "2") (pinfunction "COL_2") (pintype "passive"))
      (node (ref "KEY_F3") (pin "2") (pinfunction "COL_2") (pintype "passive"))
      (node (ref "KEY_R") (pin "2") (pinfunction "COL_2") (pintype "passive"))
      (node (ref "KEY_V") (pin "2") (pinfunction "COL_2") (pintype "passive"))
    )
    (net (code "6") (name "/COL6") (class "Default")
      (node (ref "J1") (pin "12") (pinfunction "12_12") (pintype "passive"))
      (node (ref "KEY_5") (pin "2") (pinfunction "COL_2") (pintype "passive"))
      (node (ref "KEY_B") (pin "2") (pinfunction "COL_2") (pintype "passive"))
      (node (ref "KEY_F4") (pin "2") (pinfunction "COL_2") (pintype "passive"))
      (node (ref "KEY_G") (pin "2") (pinfunction "COL_2") (pintype "passive"))
      (node (ref "KEY_Space") (pin "2") (pinfunction "COL_2") (pintype "passive"))
      (node (ref "KEY_T") (pin "2") (pinfunction "COL_2") (pintype "passive"))
    )
    (net (code "7") (name "/COL7") (class "Default")
      (node (ref "J1") (pin "13") (pinfunction "13_13") (pintype "passive"))
      (node (ref "KEY_6") (pin "2") (pinfunction "COL_2") (pintype "passive"))
      (node (ref "KEY_F5") (pin "2") (pinfunction "COL_2") (pintype "passive"))
      (node (ref "KEY_H") (pin "2") (pinfunction "COL_2") (pintype "passive"))
      (node (ref "KEY_N") (pin "2") (pinfunction "COL_2") (pintype "passive"))
      (node (ref "KEY_Y") (pin "2") (pinfunction "COL_2") (pintype "passive"))
    )
    (net (code "8") (name "/COL8") (class "Default")
      (node (ref "J1") (pin "14") (pinfunction "14_14") (pintype "passive"))
      (node (ref "KEY_7") (pin "2") (pinfunction "COL_2") (pintype "passive"))
      (node (ref "KEY_F6") (pin "2") (pinfunction "COL_2") (pintype "passive"))
      (node (ref "KEY_J") (pin "2") (pinfunction "COL_2") (pintype "passive"))
      (node (ref "KEY_M") (pin "2") (pinfunction "COL_2") (pintype "passive"))
      (node (ref "KEY_U") (pin "2") (pinfunction "COL_2") (pintype "passive"))
    )
    (net (code "9") (name "/COL9") (class "Default")
      (node (ref "J1") (pin "15") (pinfunction "15_15") (pintype "passive"))
      (node (ref "KEY_8") (pin "2") (pinfunction "COL_2") (pintype "passive"))
      (node (ref "KEY_Comma") (pin "2") (pinfunction "COL_2") (pintype "passive"))
      (node (ref "KEY_F7") (pin "2") (pinfunction "COL_2") (pintype "passive"))
      (node (ref "KEY_I") (pin "2") (pinfunction "COL_2") (pintype "passive"))
      (node (ref "KEY_K") (pin "2") (pinfunction "COL_2") (pintype "passive"))
    )
    (net (code "10") (name "/COL10") (class "Default")
      (node (ref "J1") (pin "16") (pinfunction "16_16") (pintype "passive"))
      (node (ref "KEY_9") (pin "2") (pinfunction "COL_2") (pintype "passive"))
      (node (ref "KEY_F8") (pin "2") (pinfunction "COL_2") (pintype "passive"))
      (node (ref "KEY_FullStop") (pin "2") (pinfunction "COL_2") (pintype "passive"))
      (node (ref "KEY_L") (pin "2") (pinfunction "COL_2") (pintype "passive"))
      (node (ref "KEY_O") (pin "2") (pinfunction "COL_2") (pintype "passive"))
      (node (ref "KEY_RAlt") (pin "2") (pinfunction "COL_2") (pintype "passive"))
    )
    (net (code "11") (name "/COL11") (class "Default")
      (node (ref "J1") (pin "17") (pinfunction "17_17") (pintype "passive"))
      (node (ref "KEY_0") (pin "2") (pinfunction "COL_2") (pintype "passive"))
      (node (ref "KEY_Colon") (pin "2") (pinfunction "COL_2") (pintype "passive"))
      (node (ref "KEY_F9") (pin "2") (pinfunction "COL_2") (pintype "passive"))
      (node (ref "KEY_P") (pin "2") (pinfunction "COL_2") (pintype "passive"))
      (node (ref "KEY_RWin") (pin "2") (pinfunction "COL_2") (pintype "passive"))
      (node (ref "KEY_Slash") (pin "2") (pinfunction "COL_2") (pintype "passive"))
    )
    (net (code "12") (name "/COL12") (class "Default")
      (node (ref "J1") (pin "18") (pinfunction "18_18") (pintype "passive"))
      (node (ref "KEY_F10") (pin "2") (pinfunction "COL_2") (pintype "passive"))
      (node (ref "KEY_Fn") (pin "2") (pinfunction "COL_2") (pintype "passive"))
      (node (ref "KEY_ForwardSquareBracket") (pin "2") (pinfunction "COL_2") (pintype "passive"))
      (node (ref "KEY_Quotation") (pin "2") (pinfunction "COL_2") (pintype "passive"))
      (node (ref "KEY_RShift") (pin "2") (pinfunction "COL_2") (pintype "passive"))
      (node (ref "KEY_SUB") (pin "2") (pinfunction "COL_2") (pintype "passive"))
    )
    (net (code "13") (name "/COL13") (class "Default")
      (node (ref "J1") (pin "19") (pinfunction "19_19") (pintype "passive"))
      (node (ref "KEY_ADD") (pin "2") (pinfunction "COL_2") (pintype "passive"))
      (node (ref "KEY_BackwardSquareBracket") (pin "2") (pinfunction "COL_2") (pintype "passive"))
      (node (ref "KEY_Enter") (pin "2") (pinfunction "COL_2") (pintype "passive"))
      (node (ref "KEY_F11") (pin "2") (pinfunction "COL_2") (pintype "passive"))
      (node (ref "KEY_RCtrl") (pin "2") (pinfunction "COL_2") (pintype "passive"))
    )
    (net (code "14") (name "/COL14") (class "Default")
      (node (ref "J1") (pin "20") (pinfunction "20_20") (pintype "passive"))
      (node (ref "KEY_Backslash") (pin "2") (pinfunction "COL_2") (pintype "passive"))
      (node (ref "KEY_Backspace") (pin "2") (pinfunction "COL_2") (pintype "passive"))
      (node (ref "KEY_F12") (pin "2") (pinfunction "COL_2") (pintype "passive"))
    )
    (net (code "15") (name "/COL15") (class "Default")
      (node (ref "J1") (pin "21") (pinfunction "21_21") (pintype "passive"))
      (node (ref "KEY_Delete") (pin "2") (pinfunction "COL_2") (pintype "passive"))
      (node (ref "KEY_Insert") (pin "2") (pinfunction "COL_2") (pintype "passive"))
      (node (ref "KEY_LEFT") (pin "2") (pinfunction "COL_2") (pintype "passive"))
      (node (ref "KEY_PrtSc") (pin "2") (pinfunction "COL_2") (pintype "passive"))
    )
    (net (code "16") (name "/COL16") (class "Default")
      (node (ref "J1") (pin "22") (pinfunction "22_22") (pintype "passive"))
      (node (ref "KEY_DOWN") (pin "2") (pinfunction "COL_2") (pintype "passive"))
      (node (ref "KEY_End") (pin "2") (pinfunction "COL_2") (pintype "passive"))
      (node (ref "KEY_Home") (pin "2") (pinfunction "COL_2") (pintype "passive"))
      (node (ref "KEY_ScrollLock") (pin "2") (pinfunction "COL_2") (pintype "passive"))
      (node (ref "KEY_UP") (pin "2") (pinfunction "COL_2") (pintype "passive"))
    )
    (net (code "17") (name "/COL17") (class "Default")
      (node (ref "J1") (pin "23") (pinfunction "23_23") (pintype "passive"))
      (node (ref "KEY_Pause") (pin "2") (pinfunction "COL_2") (pintype "passive"))
      (node (ref "KEY_PgDn") (pin "2") (pinfunction "COL_2") (pintype "passive"))
      (node (ref "KEY_PgUp") (pin "2") (pinfunction "COL_2") (pintype "passive"))
      (node (ref "KEY_RIGHT") (pin "2") (pinfunction "COL_2") (pintype "passive"))
    )
    (net (code "18") (name "/COL18") (class "Default")
      (node (ref "J1") (pin "24") (pinfunction "24_24") (pintype "passive"))
      (node (ref "KEY_Num0") (pin "2") (pinfunction "COL_2") (pintype "passive"))
      (node (ref "KEY_Num1") (pin "2") (pinfunction "COL_2") (pintype "passive"))
      (node (ref "KEY_Num4") (pin "2") (pinfunction "COL_2") (pintype "passive"))
      (node (ref "KEY_Num7") (pin "2") (pinfunction "COL_2") (pintype "passive"))
      (node (ref "KEY_NumLock") (pin "2") (pinfunction "COL_2") (pintype "passive"))
    )
    (net (code "19") (name "/COL19") (class "Default")
      (node (ref "J1") (pin "25") (pinfunction "25_25") (pintype "passive"))
      (node (ref "KEY_Num2") (pin "2") (pinfunction "COL_2") (pintype "passive"))
      (node (ref "KEY_Num5") (pin "2") (pinfunction "COL_2") (pintype "passive"))
      (node (ref "KEY_Num8") (pin "2") (pinfunction "COL_2") (pintype "passive"))
      (node (ref "KEY_NumDIV") (pin "2") (pinfunction "COL_2") (pintype "passive"))
    )
    (net (code "20") (name "/COL20") (class "Default")
      (node (ref "J1") (pin "26") (pinfunction "26_26") (pintype "passive"))
      (node (ref "KEY_Num3") (pin "2") (pinfunction "COL_2") (pintype "passive"))
      (node (ref "KEY_Num6") (pin "2") (pinfunction "COL_2") (pintype "passive"))
      (node (ref "KEY_Num9") (pin "2") (pinfunction "COL_2") (pintype "passive"))
      (node (ref "KEY_NumFullStop") (pin "2") (pinfunction "COL_2") (pintype "passive"))
      (node (ref "KEY_NumMUL") (pin "2") (pinfunction "COL_2") (pintype "passive"))
    )
    (net (code "21") (name "/COL21") (class "Default")
      (node (ref "J1") (pin "27") (pinfunction "27_27") (pintype "passive"))
      (node (ref "KEY_NumADD") (pin "2") (pinfunction "COL_2") (pintype "passive"))
      (node (ref "KEY_NumEnter") (pin "2") (pinfunction "COL_2") (pintype "passive"))
      (node (ref "KEY_NumSUB") (pin "2") (pinfunction "COL_2") (pintype "passive"))
    )
    (net (code "22") (name "/MCU_DOUT") (class "Default")
      (node (ref "J1") (pin "28") (pinfunction "28_28") (pintype "passive"))
      (node (ref "R0") (pin "2") (pinfunction "2_2") (pintype "passive"))
    )
    (net (code "23") (name "/ROW1") (class "Default")
      (node (ref "J1") (pin "1") (pinfunction "1_1") (pintype "passive"))
      (node (ref "R3") (pin "1") (pinfunction "1_1") (pintype "passive"))
    )
    (net (code "24") (name "/ROW2") (class "Default")
      (node (ref "J1") (pin "2") (pinfunction "2_2") (pintype "passive"))
      (node (ref "R5") (pin "1") (pinfunction "1_1") (pintype "passive"))
    )
    (net (code "25") (name "/ROW3") (class "Default")
      (node (ref "J1") (pin "3") (pinfunction "3_3") (pintype "passive"))
      (node (ref "R7") (pin "1") (pinfunction "1_1") (pintype "passive"))
    )
    (net (code "26") (name "/ROW4") (class "Default")
      (node (ref "J1") (pin "4") (pinfunction "4_4") (pintype "passive"))
      (node (ref "R9") (pin "1") (pinfunction "1_1") (pintype "passive"))
    )
    (net (code "27") (name "/ROW5") (class "Default")
      (node (ref "J1") (pin "5") (pinfunction "5_5") (pintype "passive"))
      (node (ref "R11") (pin "1") (pinfunction "1_1") (pintype "passive"))
    )
    (net (code "28") (name "/ROW6") (class "Default")
      (node (ref "J1") (pin "6") (pinfunction "6_6") (pintype "passive"))
      (node (ref "R13") (pin "1") (pinfunction "1_1") (pintype "passive"))
    )
    (net (code "29") (name "3V3") (class "Default")
      (node (ref "R10") (pin "2") (pinfunction "2_2") (pintype "passive"))
      (node (ref "R12") (pin "2") (pinfunction "2_2") (pintype "passive"))
      (node (ref "R2") (pin "2") (pinfunction "2_2") (pintype "passive"))
      (node (ref "R4") (pin "2") (pinfunction "2_2") (pintype "passive"))
      (node (ref "R6") (pin "2") (pinfunction "2_2") (pintype "passive"))
      (node (ref "R8") (pin "2") (pinfunction "2_2") (pintype "passive"))
    )
    (net (code "30") (name "5V") (class "Default")
      (node (ref "C1") (pin "2") (pinfunction "2_2") (pintype "passive"))
      (node (ref "C10") (pin "2") (pinfunction "2_2") (pintype "passive"))
      (node (ref "C100") (pin "2") (pinfunction "2_2") (pintype "passive"))
      (node (ref "C101") (pin "2") (pinfunction "2_2") (pintype "passive"))
      (node (ref "C102") (pin "2") (pinfunction "2_2") (pintype "passive"))
      (node (ref "C103") (pin "2") (pinfunction "2_2") (pintype "passive"))
      (node (ref "C104") (pin "2") (pinfunction "2_2") (pintype "passive"))
      (node (ref "C11") (pin "2") (pinfunction "2_2") (pintype "passive"))
      (node (ref "C12") (pin "2") (pinfunction "2_2") (pintype "passive"))
      (node (ref "C13") (pin "2") (pinfunction "2_2") (pintype "passive"))
      (node (ref "C14") (pin "2") (pinfunction "2_2") (pintype "passive"))
      (node (ref "C15") (pin "2") (pinfunction "2_2") (pintype "passive"))
      (node (ref "C16") (pin "2") (pinfunction "2_2") (pintype "passive"))
      (node (ref "C17") (pin "2") (pinfunction "2_2") (pintype "passive"))
      (node (ref "C18") (pin "2") (pinfunction "2_2") (pintype "passive"))
      (node (ref "C19") (pin "2") (pinfunction "2_2") (pintype "passive"))
      (node (ref "C2") (pin "2") (pinfunction "2_2") (pintype "passive"))
      (node (ref "C20") (pin "2") (pinfunction "2_2") (pintype "passive"))
      (node (ref "C21") (pin "2") (pinfunction "2_2") (pintype "passive"))
      (node (ref "C22") (pin "2") (pinfunction "2_2") (pintype "passive"))
      (node (ref "C23") (pin "2") (pinfunction "2_2") (pintype "passive"))
      (node (ref "C24") (pin "2") (pinfunction "2_2") (pintype "passive"))
      (node (ref "C25") (pin "2") (pinfunction "2_2") (pintype "passive"))
      (node (ref "C26") (pin "2") (pinfunction "2_2") (pintype "passive"))
      (node (ref "C27") (pin "2") (pinfunction "2_2") (pintype "passive"))
      (node (ref "C28") (pin "2") (pinfunction "2_2") (pintype "passive"))
      (node (ref "C29") (pin "2") (pinfunction "2_2") (pintype "passive"))
      (node (ref "C3") (pin "2") (pinfunction "2_2") (pintype "passive"))
      (node (ref "C30") (pin "2") (pinfunction "2_2") (pintype "passive"))
      (node (ref "C31") (pin "2") (pinfunction "2_2") (pintype "passive"))
      (node (ref "C32") (pin "2") (pinfunction "2_2") (pintype "passive"))
      (node (ref "C33") (pin "2") (pinfunction "2_2") (pintype "passive"))
      (node (ref "C34") (pin "2") (pinfunction "2_2") (pintype "passive"))
      (node (ref "C35") (pin "2") (pinfunction "2_2") (pintype "passive"))
      (node (ref "C36") (pin "2") (pinfunction "2_2") (pintype "passive"))
      (node (ref "C37") (pin "2") (pinfunction "2_2") (pintype "passive"))
      (node (ref "C38") (pin "2") (pinfunction "2_2") (pintype "passive"))
      (node (ref "C39") (pin "2") (pinfunction "2_2") (pintype "passive"))
      (node (ref "C4") (pin "2") (pinfunction "2_2") (pintype "passive"))
      (node (ref "C40") (pin "2") (pinfunction "2_2") (pintype "passive"))
      (node (ref "C41") (pin "2") (pinfunction "2_2") (pintype "passive"))
      (node (ref "C42") (pin "2") (pinfunction "2_2") (pintype "passive"))
      (node (ref "C43") (pin "2") (pinfunction "2_2") (pintype "passive"))
      (node (ref "C44") (pin "2") (pinfunction "2_2") (pintype "passive"))
      (node (ref "C45") (pin "2") (pinfunction "2_2") (pintype "passive"))
      (node (ref "C46") (pin "2") (pinfunction "2_2") (pintype "passive"))
      (node (ref "C47") (pin "2") (pinfunction "2_2") (pintype "passive"))
      (node (ref "C48") (pin "2") (pinfunction "2_2") (pintype "passive"))
      (node (ref "C49") (pin "2") (pinfunction "2_2") (pintype "passive"))
      (node (ref "C5") (pin "2") (pinfunction "2_2") (pintype "passive"))
      (node (ref "C50") (pin "2") (pinfunction "2_2") (pintype "passive"))
      (node (ref "C51") (pin "2") (pinfunction "2_2") (pintype "passive"))
      (node (ref "C52") (pin "2") (pinfunction "2_2") (pintype "passive"))
      (node (ref "C53") (pin "2") (pinfunction "2_2") (pintype "passive"))
      (node (ref "C54") (pin "2") (pinfunction "2_2") (pintype "passive"))
      (node (ref "C55") (pin "2") (pinfunction "2_2") (pintype "passive"))
      (node (ref "C56") (pin "2") (pinfunction "2_2") (pintype "passive"))
      (node (ref "C57") (pin "2") (pinfunction "2_2") (pintype "passive"))
      (node (ref "C58") (pin "2") (pinfunction "2_2") (pintype "passive"))
      (node (ref "C59") (pin "2") (pinfunction "2_2") (pintype "passive"))
      (node (ref "C6") (pin "2") (pinfunction "2_2") (pintype "passive"))
      (node (ref "C60") (pin "2") (pinfunction "2_2") (pintype "passive"))
      (node (ref "C61") (pin "2") (pinfunction "2_2") (pintype "passive"))
      (node (ref "C62") (pin "2") (pinfunction "2_2") (pintype "passive"))
      (node (ref "C63") (pin "2") (pinfunction "2_2") (pintype "passive"))
      (node (ref "C64") (pin "2") (pinfunction "2_2") (pintype "passive"))
      (node (ref "C65") (pin "2") (pinfunction "2_2") (pintype "passive"))
      (node (ref "C66") (pin "2") (pinfunction "2_2") (pintype "passive"))
      (node (ref "C67") (pin "2") (pinfunction "2_2") (pintype "passive"))
      (node (ref "C68") (pin "2") (pinfunction "2_2") (pintype "passive"))
      (node (ref "C69") (pin "2") (pinfunction "2_2") (pintype "passive"))
      (node (ref "C7") (pin "2") (pinfunction "2_2") (pintype "passive"))
      (node (ref "C70") (pin "2") (pinfunction "2_2") (pintype "passive"))
      (node (ref "C71") (pin "2") (pinfunction "2_2") (pintype "passive"))
      (node (ref "C72") (pin "2") (pinfunction "2_2") (pintype "passive"))
      (node (ref "C73") (pin "2") (pinfunction "2_2") (pintype "passive"))
      (node (ref "C74") (pin "2") (pinfunction "2_2") (pintype "passive"))
      (node (ref "C75") (pin "2") (pinfunction "2_2") (pintype "passive"))
      (node (ref "C76") (pin "2") (pinfunction "2_2") (pintype "passive"))
      (node (ref "C77") (pin "2") (pinfunction "2_2") (pintype "passive"))
      (node (ref "C78") (pin "2") (pinfunction "2_2") (pintype "passive"))
      (node (ref "C79") (pin "2") (pinfunction "2_2") (pintype "passive"))
      (node (ref "C8") (pin "2") (pinfunction "2_2") (pintype "passive"))
      (node (ref "C80") (pin "2") (pinfunction "2_2") (pintype "passive"))
      (node (ref "C81") (pin "2") (pinfunction "2_2") (pintype "passive"))
      (node (ref "C82") (pin "2") (pinfunction "2_2") (pintype "passive"))
      (node (ref "C83") (pin "2") (pinfunction "2_2") (pintype "passive"))
      (node (ref "C84") (pin "2") (pinfunction "2_2") (pintype "passive"))
      (node (ref "C85") (pin "2") (pinfunction "2_2") (pintype "passive"))
      (node (ref "C86") (pin "2") (pinfunction "2_2") (pintype "passive"))
      (node (ref "C87") (pin "2") (pinfunction "2_2") (pintype "passive"))
      (node (ref "C88") (pin "2") (pinfunction "2_2") (pintype "passive"))
      (node (ref "C89") (pin "2") (pinfunction "2_2") (pintype "passive"))
      (node (ref "C9") (pin "2") (pinfunction "2_2") (pintype "passive"))
      (node (ref "C90") (pin "2") (pinfunction "2_2") (pintype "passive"))
      (node (ref "C91") (pin "2") (pinfunction "2_2") (pintype "passive"))
      (node (ref "C92") (pin "2") (pinfunction "2_2") (pintype "passive"))
      (node (ref "C93") (pin "2") (pinfunction "2_2") (pintype "passive"))
      (node (ref "C94") (pin "2") (pinfunction "2_2") (pintype "passive"))
      (node (ref "C95") (pin "2") (pinfunction "2_2") (pintype "passive"))
      (node (ref "C96") (pin "2") (pinfunction "2_2") (pintype "passive"))
      (node (ref "C97") (pin "2") (pinfunction "2_2") (pintype "passive"))
      (node (ref "C98") (pin "2") (pinfunction "2_2") (pintype "passive"))
      (node (ref "C99") (pin "2") (pinfunction "2_2") (pintype "passive"))
      (node (ref "J1") (pin "31") (pinfunction "31_31") (pintype "passive"))
      (node (ref "J1") (pin "32") (pinfunction "32_32") (pintype "passive"))
      (node (ref "J1") (pin "33") (pinfunction "33_33") (pintype "passive"))
      (node (ref "J1") (pin "34") (pinfunction "34_34") (pintype "passive"))
      (node (ref "J1") (pin "35") (pinfunction "35_35") (pintype "passive"))
      (node (ref "KEY_0") (pin "5") (pinfunction "VCC_5") (pintype "passive"))
      (node (ref "KEY_1") (pin "5") (pinfunction "VCC_5") (pintype "passive"))
      (node (ref "KEY_2") (pin "5") (pinfunction "VCC_5") (pintype "passive"))
      (node (ref "KEY_3") (pin "5") (pinfunction "VCC_5") (pintype "passive"))
      (node (ref "KEY_4") (pin "5") (pinfunction "VCC_5") (pintype "passive"))
      (node (ref "KEY_5") (pin "5") (pinfunction "VCC_5") (pintype "passive"))
      (node (ref "KEY_6") (pin "5") (pinfunction "VCC_5") (pintype "passive"))
      (node (ref "KEY_7") (pin "5") (pinfunction "VCC_5") (pintype "passive"))
      (node (ref "KEY_8") (pin "5") (pinfunction "VCC_5") (pintype "passive"))
      (node (ref "KEY_9") (pin "5") (pinfunction "VCC_5") (pintype "passive"))
      (node (ref "KEY_A") (pin "5") (pinfunction "VCC_5") (pintype "passive"))
      (node (ref "KEY_ADD") (pin "5") (pinfunction "VCC_5") (pintype "passive"))
      (node (ref "KEY_B") (pin "5") (pinfunction "VCC_5") (pintype "passive"))
      (node (ref "KEY_Backslash") (pin "5") (pinfunction "VCC_5") (pintype "passive"))
      (node (ref "KEY_Backspace") (pin "5") (pinfunction "VCC_5") (pintype "passive"))
      (node (ref "KEY_BackwardSquareBracket") (pin "5") (pinfunction "VCC_5") (pintype "passive"))
      (node (ref "KEY_C") (pin "5") (pinfunction "VCC_5") (pintype "passive"))
      (node (ref "KEY_CapsLock") (pin "5") (pinfunction "VCC_5") (pintype "passive"))
      (node (ref "KEY_Colon") (pin "5") (pinfunction "VCC_5") (pintype "passive"))
      (node (ref "KEY_Comma") (pin "5") (pinfunction "VCC_5") (pintype "passive"))
      (node (ref "KEY_D") (pin "5") (pinfunction "VCC_5") (pintype "passive"))
      (node (ref "KEY_DOWN") (pin "5") (pinfunction "VCC_5") (pintype "passive"))
      (node (ref "KEY_Delete") (pin "5") (pinfunction "VCC_5") (pintype "passive"))
      (node (ref "KEY_E") (pin "5") (pinfunction "VCC_5") (pintype "passive"))
      (node (ref "KEY_ESC") (pin "5") (pinfunction "VCC_5") (pintype "passive"))
      (node (ref "KEY_End") (pin "5") (pinfunction "VCC_5") (pintype "passive"))
      (node (ref "KEY_Enter") (pin "5") (pinfunction "VCC_5") (pintype "passive"))
      (node (ref "KEY_F") (pin "5") (pinfunction "VCC_5") (pintype "passive"))
      (node (ref "KEY_F1") (pin "5") (pinfunction "VCC_5") (pintype "passive"))
      (node (ref "KEY_F10") (pin "5") (pinfunction "VCC_5") (pintype "passive"))
      (node (ref "KEY_F11") (pin "5") (pinfunction "VCC_5") (pintype "passive"))
      (node (ref "KEY_F12") (pin "5") (pinfunction "VCC_5") (pintype "passive"))
      (node (ref "KEY_F2") (pin "5") (pinfunction "VCC_5") (pintype "passive"))
      (node (ref "KEY_F3") (pin "5") (pinfunction "VCC_5") (pintype "passive"))
      (node (ref "KEY_F4") (pin "5") (pinfunction "VCC_5") (pintype "passive"))
      (node (ref "KEY_F5") (pin "5") (pinfunction "VCC_5") (pintype "passive"))
      (node (ref "KEY_F6") (pin "5") (pinfunction "VCC_5") (pintype "passive"))
      (node (ref "KEY_F7") (pin "5") (pinfunction "VCC_5") (pintype "passive"))
      (node (ref "KEY_F8") (pin "5") (pinfunction "VCC_5") (pintype "passive"))
      (node (ref "KEY_F9") (pin "5") (pinfunction "VCC_5") (pintype "passive"))
      (node (ref "KEY_Fn") (pin "5") (pinfunction "VCC_5") (pintype "passive"))
      (node (ref "KEY_ForwardSquareBracket") (pin "5") (pinfunction "VCC_5") (pintype "passive"))
      (node (ref "KEY_FullStop") (pin "5") (pinfunction "VCC_5") (pintype "passive"))
      (node (ref "KEY_G") (pin "5") (pinfunction "VCC_5") (pintype "passive"))
      (node (ref "KEY_H") (pin "5") (pinfunction "VCC_5") (pintype "passive"))
      (node (ref "KEY_Home") (pin "5") (pinfunction "VCC_5") (pintype "passive"))
      (node (ref "KEY_I") (pin "5") (pinfunction "VCC_5") (pintype "passive"))
      (node (ref "KEY_Insert") (pin "5") (pinfunction "VCC_5") (pintype "passive"))
      (node (ref "KEY_J") (pin "5") (pinfunction "VCC_5") (pintype "passive"))
      (node (ref "KEY_K") (pin "5") (pinfunction "VCC_5") (pintype "passive"))
      (node (ref "KEY_L") (pin "5") (pinfunction "VCC_5") (pintype "passive"))
      (node (ref "KEY_LAlt") (pin "5") (pinfunction "VCC_5") (pintype "passive"))
      (node (ref "KEY_LCtrl") (pin "5") (pinfunction "VCC_5") (pintype "passive"))
      (node (ref "KEY_LEFT") (pin "5") (pinfunction "VCC_5") (pintype "passive"))
      (node (ref "KEY_LShift") (pin "5") (pinfunction "VCC_5") (pintype "passive"))
      (node (ref "KEY_LWin") (pin "5") (pinfunction "VCC_5") (pintype "passive"))
      (node (ref "KEY_M") (pin "5") (pinfunction "VCC_5") (pintype "passive"))
      (node (ref "KEY_N") (pin "5") (pinfunction "VCC_5") (pintype "passive"))
      (node (ref "KEY_Num0") (pin "5") (pinfunction "VCC_5") (pintype "passive"))
      (node (ref "KEY_Num1") (pin "5") (pinfunction "VCC_5") (pintype "passive"))
      (node (ref "KEY_Num2") (pin "5") (pinfunction "VCC_5") (pintype "passive"))
      (node (ref "KEY_Num3") (pin "5") (pinfunction "VCC_5") (pintype "passive"))
      (node (ref "KEY_Num4") (pin "5") (pinfunction "VCC_5") (pintype "passive"))
      (node (ref "KEY_Num5") (pin "5") (pinfunction "VCC_5") (pintype "passive"))
      (node (ref "KEY_Num6") (pin "5") (pinfunction "VCC_5") (pintype "passive"))
      (node (ref "KEY_Num7") (pin "5") (pinfunction "VCC_5") (pintype "passive"))
      (node (ref "KEY_Num8") (pin "5") (pinfunction "VCC_5") (pintype "passive"))
      (node (ref "KEY_Num9") (pin "5") (pinfunction "VCC_5") (pintype "passive"))
      (node (ref "KEY_NumADD") (pin "5") (pinfunction "VCC_5") (pintype "passive"))
      (node (ref "KEY_NumDIV") (pin "5") (pinfunction "VCC_5") (pintype "passive"))
      (node (ref "KEY_NumEnter") (pin "5") (pinfunction "VCC_5") (pintype "passive"))
      (node (ref "KEY_NumFullStop") (pin "5") (pinfunction "VCC_5") (pintype "passive"))
      (node (ref "KEY_NumLock") (pin "5") (pinfunction "VCC_5") (pintype "passive"))
      (node (ref "KEY_NumMUL") (pin "5") (pinfunction "VCC_5") (pintype "passive"))
      (node (ref "KEY_NumSUB") (pin "5") (pinfunction "VCC_5") (pintype "passive"))
      (node (ref "KEY_O") (pin "5") (pinfunction "VCC_5") (pintype "passive"))
      (node (ref "KEY_P") (pin "5") (pinfunction "VCC_5") (pintype "passive"))
      (node (ref "KEY_Pause") (pin "5") (pinfunction "VCC_5") (pintype "passive"))
      (node (ref "KEY_PgDn") (pin "5") (pinfunction "VCC_5") (pintype "passive"))
      (node (ref "KEY_PgUp") (pin "5") (pinfunction "VCC_5") (pintype "passive"))
      (node (ref "KEY_PrtSc") (pin "5") (pinfunction "VCC_5") (pintype "passive"))
      (node (ref "KEY_Q") (pin "5") (pinfunction "VCC_5") (pintype "passive"))
      (node (ref "KEY_Quotation") (pin "5") (pinfunction "VCC_5") (pintype "passive"))
      (node (ref "KEY_R") (pin "5") (pinfunction "VCC_5") (pintype "passive"))
      (node (ref "KEY_RAlt") (pin "5") (pinfunction "VCC_5") (pintype "passive"))
      (node (ref "KEY_RCtrl") (pin "5") (pinfunction "VCC_5") (pintype "passive"))
      (node (ref "KEY_RIGHT") (pin "5") (pinfunction "VCC_5") (pintype "passive"))
      (node (ref "KEY_RShift") (pin "5") (pinfunction "VCC_5") (pintype "passive"))
      (node (ref "KEY_RWin") (pin "5") (pinfunction "VCC_5") (pintype "passive"))
      (node (ref "KEY_S") (pin "5") (pinfunction "VCC_5") (pintype "passive"))
      (node (ref "KEY_SUB") (pin "5") (pinfunction "VCC_5") (pintype "passive"))
      (node (ref "KEY_ScrollLock") (pin "5") (pinfunction "VCC_5") (pintype "passive"))
      (node (ref "KEY_Slash") (pin "5") (pinfunction "VCC_5") (pintype "passive"))
      (node (ref "KEY_Space") (pin "5") (pinfunction "VCC_5") (pintype "passive"))
      (node (ref "KEY_T") (pin "5") (pinfunction "VCC_5") (pintype "passive"))
      (node (ref "KEY_Tab") (pin "5") (pinfunction "VCC_5") (pintype "passive"))
      (node (ref "KEY_U") (pin "5") (pinfunction "VCC_5") (pintype "passive"))
      (node (ref "KEY_UP") (pin "5") (pinfunction "VCC_5") (pintype "passive"))
      (node (ref "KEY_V") (pin "5") (pinfunction "VCC_5") (pintype "passive"))
      (node (ref "KEY_W") (pin "5") (pinfunction "VCC_5") (pintype "passive"))
      (node (ref "KEY_WAVE") (pin "5") (pinfunction "VCC_5") (pintype "passive"))
      (node (ref "KEY_X") (pin "5") (pinfunction "VCC_5") (pintype "passive"))
      (node (ref "KEY_Y") (pin "5") (pinfunction "VCC_5") (pintype "passive"))
      (node (ref "KEY_Z") (pin "5") (pinfunction "VCC_5") (pintype "passive"))
    )
    (net (code "31") (name "GND") (class "Default")
      (node (ref "C1") (pin "1") (pinfunction "1_1") (pintype "passive"))
      (node (ref "C10") (pin "1") (pinfunction "1_1") (pintype "passive"))
      (node (ref "C100") (pin "1") (pinfunction "1_1") (pintype "passive"))
      (node (ref "C101") (pin "1") (pinfunction "1_1") (pintype "passive"))
      (node (ref "C102") (pin "1") (pinfunction "1_1") (pintype "passive"))
      (node (ref "C103") (pin "1") (pinfunction "1_1") (pintype "passive"))
      (node (ref "C104") (pin "1") (pinfunction "1_1") (pintype "passive"))
      (node (ref "C11") (pin "1") (pinfunction "1_1") (pintype "passive"))
      (node (ref "C12") (pin "1") (pinfunction "1_1") (pintype "passive"))
      (node (ref "C13") (pin "1") (pinfunction "1_1") (pintype "passive"))
      (node (ref "C14") (pin "1") (pinfunction "1_1") (pintype "passive"))
      (node (ref "C15") (pin "1") (pinfunction "1_1") (pintype "passive"))
      (node (ref "C16") (pin "1") (pinfunction "1_1") (pintype "passive"))
      (node (ref "C17") (pin "1") (pinfunction "1_1") (pintype "passive"))
      (node (ref "C18") (pin "1") (pinfunction "1_1") (pintype "passive"))
      (node (ref "C19") (pin "1") (pinfunction "1_1") (pintype "passive"))
      (node (ref "C2") (pin "1") (pinfunction "1_1") (pintype "passive"))
      (node (ref "C20") (pin "1") (pinfunction "1_1") (pintype "passive"))
      (node (ref "C21") (pin "1") (pinfunction "1_1") (pintype "passive"))
      (node (ref "C22") (pin "1") (pinfunction "1_1") (pintype "passive"))
      (node (ref "C23") (pin "1") (pinfunction "1_1") (pintype "passive"))
      (node (ref "C24") (pin "1") (pinfunction "1_1") (pintype "passive"))
      (node (ref "C25") (pin "1") (pinfunction "1_1") (pintype "passive"))
      (node (ref "C26") (pin "1") (pinfunction "1_1") (pintype "passive"))
      (node (ref "C27") (pin "1") (pinfunction "1_1") (pintype "passive"))
      (node (ref "C28") (pin "1") (pinfunction "1_1") (pintype "passive"))
      (node (ref "C29") (pin "1") (pinfunction "1_1") (pintype "passive"))
      (node (ref "C3") (pin "1") (pinfunction "1_1") (pintype "passive"))
      (node (ref "C30") (pin "1") (pinfunction "1_1") (pintype "passive"))
      (node (ref "C31") (pin "1") (pinfunction "1_1") (pintype "passive"))
      (node (ref "C32") (pin "1") (pinfunction "1_1") (pintype "passive"))
      (node (ref "C33") (pin "1") (pinfunction "1_1") (pintype "passive"))
      (node (ref "C34") (pin "1") (pinfunction "1_1") (pintype "passive"))
      (node (ref "C35") (pin "1") (pinfunction "1_1") (pintype "passive"))
      (node (ref "C36") (pin "1") (pinfunction "1_1") (pintype "passive"))
      (node (ref "C37") (pin "1") (pinfunction "1_1") (pintype "passive"))
      (node (ref "C38") (pin "1") (pinfunction "1_1") (pintype "passive"))
      (node (ref "C39") (pin "1") (pinfunction "1_1") (pintype "passive"))
      (node (ref "C4") (pin "1") (pinfunction "1_1") (pintype "passive"))
      (node (ref "C40") (pin "1") (pinfunction "1_1") (pintype "passive"))
      (node (ref "C41") (pin "1") (pinfunction "1_1") (pintype "passive"))
      (node (ref "C42") (pin "1") (pinfunction "1_1") (pintype "passive"))
      (node (ref "C43") (pin "1") (pinfunction "1_1") (pintype "passive"))
      (node (ref "C44") (pin "1") (pinfunction "1_1") (pintype "passive"))
      (node (ref "C45") (pin "1") (pinfunction "1_1") (pintype "passive"))
      (node (ref "C46") (pin "1") (pinfunction "1_1") (pintype "passive"))
      (node (ref "C47") (pin "1") (pinfunction "1_1") (pintype "passive"))
      (node (ref "C48") (pin "1") (pinfunction "1_1") (pintype "passive"))
      (node (ref "C49") (pin "1") (pinfunction "1_1") (pintype "passive"))
      (node (ref "C5") (pin "1") (pinfunction "1_1") (pintype "passive"))
      (node (ref "C50") (pin "1") (pinfunction "1_1") (pintype "passive"))
      (node (ref "C51") (pin "1") (pinfunction "1_1") (pintype "passive"))
      (node (ref "C52") (pin "1") (pinfunction "1_1") (pintype "passive"))
      (node (ref "C53") (pin "1") (pinfunction "1_1") (pintype "passive"))
      (node (ref "C54") (pin "1") (pinfunction "1_1") (pintype "passive"))
      (node (ref "C55") (pin "1") (pinfunction "1_1") (pintype "passive"))
      (node (ref "C56") (pin "1") (pinfunction "1_1") (pintype "passive"))
      (node (ref "C57") (pin "1") (pinfunction "1_1") (pintype "passive"))
      (node (ref "C58") (pin "1") (pinfunction "1_1") (pintype "passive"))
      (node (ref "C59") (pin "1") (pinfunction "1_1") (pintype "passive"))
      (node (ref "C6") (pin "1") (pinfunction "1_1") (pintype "passive"))
      (node (ref "C60") (pin "1") (pinfunction "1_1") (pintype "passive"))
      (node (ref "C61") (pin "1") (pinfunction "1_1") (pintype "passive"))
      (node (ref "C62") (pin "1") (pinfunction "1_1") (pintype "passive"))
      (node (ref "C63") (pin "1") (pinfunction "1_1") (pintype "passive"))
      (node (ref "C64") (pin "1") (pinfunction "1_1") (pintype "passive"))
      (node (ref "C65") (pin "1") (pinfunction "1_1") (pintype "passive"))
      (node (ref "C66") (pin "1") (pinfunction "1_1") (pintype "passive"))
      (node (ref "C67") (pin "1") (pinfunction "1_1") (pintype "passive"))
      (node (ref "C68") (pin "1") (pinfunction "1_1") (pintype "passive"))
      (node (ref "C69") (pin "1") (pinfunction "1_1") (pintype "passive"))
      (node (ref "C7") (pin "1") (pinfunction "1_1") (pintype "passive"))
      (node (ref "C70") (pin "1") (pinfunction "1_1") (pintype "passive"))
      (node (ref "C71") (pin "1") (pinfunction "1_1") (pintype "passive"))
      (node (ref "C72") (pin "1") (pinfunction "1_1") (pintype "passive"))
      (node (ref "C73") (pin "1") (pinfunction "1_1") (pintype "passive"))
      (node (ref "C74") (pin "1") (pinfunction "1_1") (pintype "passive"))
      (node (ref "C75") (pin "1") (pinfunction "1_1") (pintype "passive"))
      (node (ref "C76") (pin "1") (pinfunction "1_1") (pintype "passive"))
      (node (ref "C77") (pin "1") (pinfunction "1_1") (pintype "passive"))
      (node (ref "C78") (pin "1") (pinfunction "1_1") (pintype "passive"))
      (node (ref "C79") (pin "1") (pinfunction "1_1") (pintype "passive"))
      (node (ref "C8") (pin "1") (pinfunction "1_1") (pintype "passive"))
      (node (ref "C80") (pin "1") (pinfunction "1_1") (pintype "passive"))
      (node (ref "C81") (pin "1") (pinfunction "1_1") (pintype "passive"))
      (node (ref "C82") (pin "1") (pinfunction "1_1") (pintype "passive"))
      (node (ref "C83") (pin "1") (pinfunction "1_1") (pintype "passive"))
      (node (ref "C84") (pin "1") (pinfunction "1_1") (pintype "passive"))
      (node (ref "C85") (pin "1") (pinfunction "1_1") (pintype "passive"))
      (node (ref "C86") (pin "1") (pinfunction "1_1") (pintype "passive"))
      (node (ref "C87") (pin "1") (pinfunction "1_1") (pintype "passive"))
      (node (ref "C88") (pin "1") (pinfunction "1_1") (pintype "passive"))
      (node (ref "C89") (pin "1") (pinfunction "1_1") (pintype "passive"))
      (node (ref "C9") (pin "1") (pinfunction "1_1") (pintype "passive"))
      (node (ref "C90") (pin "1") (pinfunction "1_1") (pintype "passive"))
      (node (ref "C91") (pin "1") (pinfunction "1_1") (pintype "passive"))
      (node (ref "C92") (pin "1") (pinfunction "1_1") (pintype "passive"))
      (node (ref "C93") (pin "1") (pinfunction "1_1") (pintype "passive"))
      (node (ref "C94") (pin "1") (pinfunction "1_1") (pintype "passive"))
      (node (ref "C95") (pin "1") (pinfunction "1_1") (pintype "passive"))
      (node (ref "C96") (pin "1") (pinfunction "1_1") (pintype "passive"))
      (node (ref "C97") (pin "1") (pinfunction "1_1") (pintype "passive"))
      (node (ref "C98") (pin "1") (pinfunction "1_1") (pintype "passive"))
      (node (ref "C99") (pin "1") (pinfunction "1_1") (pintype "passive"))
      (node (ref "J1") (pin "36") (pinfunction "36_36") (pintype "passive"))
      (node (ref "J1") (pin "37") (pinfunction "37_37") (pintype "passive"))
      (node (ref "J1") (pin "38") (pinfunction "38_38") (pintype "passive"))
      (node (ref "J1") (pin "39") (pinfunction "39_39") (pintype "passive"))
      (node (ref "J1") (pin "40") (pinfunction "40_40") (pintype "passive"))
      (node (ref "KEY_0") (pin "6") (pinfunction "GND_6") (pintype "passive"))
      (node (ref "KEY_1") (pin "6") (pinfunction "GND_6") (pintype "passive"))
      (node (ref "KEY_2") (pin "6") (pinfunction "GND_6") (pintype "passive"))
      (node (ref "KEY_3") (pin "6") (pinfunction "GND_6") (pintype "passive"))
      (node (ref "KEY_4") (pin "6") (pinfunction "GND_6") (pintype "passive"))
      (node (ref "KEY_5") (pin "6") (pinfunction "GND_6") (pintype "passive"))
      (node (ref "KEY_6") (pin "6") (pinfunction "GND_6") (pintype "passive"))
      (node (ref "KEY_7") (pin "6") (pinfunction "GND_6") (pintype "passive"))
      (node (ref "KEY_8") (pin "6") (pinfunction "GND_6") (pintype "passive"))
      (node (ref "KEY_9") (pin "6") (pinfunction "GND_6") (pintype "passive"))
      (node (ref "KEY_A") (pin "6") (pinfunction "GND_6") (pintype "passive"))
      (node (ref "KEY_ADD") (pin "6") (pinfunction "GND_6") (pintype "passive"))
      (node (ref "KEY_B") (pin "6") (pinfunction "GND_6") (pintype "passive"))
      (node (ref "KEY_Backslash") (pin "6") (pinfunction "GND_6") (pintype "passive"))
      (node (ref "KEY_Backspace") (pin "6") (pinfunction "GND_6") (pintype "passive"))
      (node (ref "KEY_BackwardSquareBracket") (pin "6") (pinfunction "GND_6") (pintype "passive"))
      (node (ref "KEY_C") (pin "6") (pinfunction "GND_6") (pintype "passive"))
      (node (ref "KEY_CapsLock") (pin "6") (pinfunction "GND_6") (pintype "passive"))
      (node (ref "KEY_Colon") (pin "6") (pinfunction "GND_6") (pintype "passive"))
      (node (ref "KEY_Comma") (pin "6") (pinfunction "GND_6") (pintype "passive"))
      (node (ref "KEY_D") (pin "6") (pinfunction "GND_6") (pintype "passive"))
      (node (ref "KEY_DOWN") (pin "6") (pinfunction "GND_6") (pintype "passive"))
      (node (ref "KEY_Delete") (pin "6") (pinfunction "GND_6") (pintype "passive"))
      (node (ref "KEY_E") (pin "6") (pinfunction "GND_6") (pintype "passive"))
      (node (ref "KEY_ESC") (pin "6") (pinfunction "GND_6") (pintype "passive"))
      (node (ref "KEY_End") (pin "6") (pinfunction "GND_6") (pintype "passive"))
      (node (ref "KEY_Enter") (pin "6") (pinfunction "GND_6") (pintype "passive"))
      (node (ref "KEY_F") (pin "6") (pinfunction "GND_6") (pintype "passive"))
      (node (ref "KEY_F1") (pin "6") (pinfunction "GND_6") (pintype "passive"))
      (node (ref "KEY_F10") (pin "6") (pinfunction "GND_6") (pintype "passive"))
      (node (ref "KEY_F11") (pin "6") (pinfunction "GND_6") (pintype "passive"))
      (node (ref "KEY_F12") (pin "6") (pinfunction "GND_6") (pintype "passive"))
      (node (ref "KEY_F2") (pin "6") (pinfunction "GND_6") (pintype "passive"))
      (node (ref "KEY_F3") (pin "6") (pinfunction "GND_6") (pintype "passive"))
      (node (ref "KEY_F4") (pin "6") (pinfunction "GND_6") (pintype "passive"))
      (node (ref "KEY_F5") (pin "6") (pinfunction "GND_6") (pintype "passive"))
      (node (ref "KEY_F6") (pin "6") (pinfunction "GND_6") (pintype "passive"))
      (node (ref "KEY_F7") (pin "6") (pinfunction "GND_6") (pintype "passive"))
      (node (ref "KEY_F8") (pin "6") (pinfunction "GND_6") (pintype "passive"))
      (node (ref "KEY_F9") (pin "6") (pinfunction "GND_6") (pintype "passive"))
      (node (ref "KEY_Fn") (pin "6") (pinfunction "GND_6") (pintype "passive"))
      (node (ref "KEY_ForwardSquareBracket") (pin "6") (pinfunction "GND_6") (pintype "passive"))
      (node (ref "KEY_FullStop") (pin "6") (pinfunction "GND_6") (pintype "passive"))
      (node (ref "KEY_G") (pin "6") (pinfunction "GND_6") (pintype "passive"))
      (node (ref "KEY_H") (pin "6") (pinfunction "GND_6") (pintype "passive"))
      (node (ref "KEY_Home") (pin "6") (pinfunction "GND_6") (pintype "passive"))
      (node (ref "KEY_I") (pin "6") (pinfunction "GND_6") (pintype "passive"))
      (node (ref "KEY_Insert") (pin "6") (pinfunction "GND_6") (pintype "passive"))
      (node (ref "KEY_J") (pin "6") (pinfunction "GND_6") (pintype "passive"))
      (node (ref "KEY_K") (pin "6") (pinfunction "GND_6") (pintype "passive"))
      (node (ref "KEY_L") (pin "6") (pinfunction "GND_6") (pintype "passive"))
      (node (ref "KEY_LAlt") (pin "6") (pinfunction "GND_6") (pintype "passive"))
      (node (ref "KEY_LCtrl") (pin "6") (pinfunction "GND_6") (pintype "passive"))
      (node (ref "KEY_LEFT") (pin "6") (pinfunction "GND_6") (pintype "passive"))
      (node (ref "KEY_LShift") (pin "6") (pinfunction "GND_6") (pintype "passive"))
      (node (ref "KEY_LWin") (pin "6") (pinfunction "GND_6") (pintype "passive"))
      (node (ref "KEY_M") (pin "6") (pinfunction "GND_6") (pintype "passive"))
      (node (ref "KEY_N") (pin "6") (pinfunction "GND_6") (pintype "passive"))
      (node (ref "KEY_Num0") (pin "6") (pinfunction "GND_6") (pintype "passive"))
      (node (ref "KEY_Num1") (pin "6") (pinfunction "GND_6") (pintype "passive"))
      (node (ref "KEY_Num2") (pin "6") (pinfunction "GND_6") (pintype "passive"))
      (node (ref "KEY_Num3") (pin "6") (pinfunction "GND_6") (pintype "passive"))
      (node (ref "KEY_Num4") (pin "6") (pinfunction "GND_6") (pintype "passive"))
      (node (ref "KEY_Num5") (pin "6") (pinfunction "GND_6") (pintype "passive"))
      (node (ref "KEY_Num6") (pin "6") (pinfunction "GND_6") (pintype "passive"))
      (node (ref "KEY_Num7") (pin "6") (pinfunction "GND_6") (pintype "passive"))
      (node (ref "KEY_Num8") (pin "6") (pinfunction "GND_6") (pintype "passive"))
      (node (ref "KEY_Num9") (pin "6") (pinfunction "GND_6") (pintype "passive"))
      (node (ref "KEY_NumADD") (pin "6") (pinfunction "GND_6") (pintype "passive"))
      (node (ref "KEY_NumDIV") (pin "6") (pinfunction "GND_6") (pintype "passive"))
      (node (ref "KEY_NumEnter") (pin "6") (pinfunction "GND_6") (pintype "passive"))
      (node (ref "KEY_NumFullStop") (pin "6") (pinfunction "GND_6") (pintype "passive"))
      (node (ref "KEY_NumLock") (pin "6") (pinfunction "GND_6") (pintype "passive"))
      (node (ref "KEY_NumMUL") (pin "6") (pinfunction "GND_6") (pintype "passive"))
      (node (ref "KEY_NumSUB") (pin "6") (pinfunction "GND_6") (pintype "passive"))
      (node (ref "KEY_O") (pin "6") (pinfunction "GND_6") (pintype "passive"))
      (node (ref "KEY_P") (pin "6") (pinfunction "GND_6") (pintype "passive"))
      (node (ref "KEY_Pause") (pin "6") (pinfunction "GND_6") (pintype "passive"))
      (node (ref "KEY_PgDn") (pin "6") (pinfunction "GND_6") (pintype "passive"))
      (node (ref "KEY_PgUp") (pin "6") (pinfunction "GND_6") (pintype "passive"))
      (node (ref "KEY_PrtSc") (pin "6") (pinfunction "GND_6") (pintype "passive"))
      (node (ref "KEY_Q") (pin "6") (pinfunction "GND_6") (pintype "passive"))
      (node (ref "KEY_Quotation") (pin "6") (pinfunction "GND_6") (pintype "passive"))
      (node (ref "KEY_R") (pin "6") (pinfunction "GND_6") (pintype "passive"))
      (node (ref "KEY_RAlt") (pin "6") (pinfunction "GND_6") (pintype "passive"))
      (node (ref "KEY_RCtrl") (pin "6") (pinfunction "GND_6") (pintype "passive"))
      (node (ref "KEY_RIGHT") (pin "6") (pinfunction "GND_6") (pintype "passive"))
      (node (ref "KEY_RShift") (pin "6") (pinfunction "GND_6") (pintype "passive"))
      (node (ref "KEY_RWin") (pin "6") (pinfunction "GND_6") (pintype "passive"))
      (node (ref "KEY_S") (pin "6") (pinfunction "GND_6") (pintype "passive"))
      (node (ref "KEY_SUB") (pin "6") (pinfunction "GND_6") (pintype "passive"))
      (node (ref "KEY_ScrollLock") (pin "6") (pinfunction "GND_6") (pintype "passive"))
      (node (ref "KEY_Slash") (pin "6") (pinfunction "GND_6") (pintype "passive"))
      (node (ref "KEY_Space") (pin "6") (pinfunction "GND_6") (pintype "passive"))
      (node (ref "KEY_T") (pin "6") (pinfunction "GND_6") (pintype "passive"))
      (node (ref "KEY_Tab") (pin "6") (pinfunction "GND_6") (pintype "passive"))
      (node (ref "KEY_U") (pin "6") (pinfunction "GND_6") (pintype "passive"))
      (node (ref "KEY_UP") (pin "6") (pinfunction "GND_6") (pintype "passive"))
      (node (ref "KEY_V") (pin "6") (pinfunction "GND_6") (pintype "passive"))
      (node (ref "KEY_W") (pin "6") (pinfunction "GND_6") (pintype "passive"))
      (node (ref "KEY_WAVE") (pin "6") (pinfunction "GND_6") (pintype "passive"))
      (node (ref "KEY_X") (pin "6") (pinfunction "GND_6") (pintype "passive"))
      (node (ref "KEY_Y") (pin "6") (pinfunction "GND_6") (pintype "passive"))
      (node (ref "KEY_Z") (pin "6") (pinfunction "GND_6") (pintype "passive"))
    )
    (net (code "32") (name "Net-(KEY_0-DI)") (class "Default")
      (node (ref "KEY_0") (pin "4") (pinfunction "DI_4") (pintype "passive"))
      (node (ref "KEY_SUB") (pin "3") (pinfunction "DO_3") (pintype "passive"))
    )
    (net (code "33") (name "Net-(KEY_0-DO)") (class "Default")
      (node (ref "KEY_0") (pin "3") (pinfunction "DO_3") (pintype "passive"))
      (node (ref "KEY_9") (pin "4") (pinfunction "DI_4") (pintype "passive"))
    )
    (net (code "34") (name "Net-(KEY_0-ROW)") (class "Default")
      (node (ref "KEY_0") (pin "1") (pinfunction "ROW_1") (pintype "passive"))
      (node (ref "KEY_1") (pin "1") (pinfunction "ROW_1") (pintype "passive"))
      (node (ref "KEY_2") (pin "1") (pinfunction "ROW_1") (pintype "passive"))
      (node (ref "KEY_3") (pin "1") (pinfunction "ROW_1") (pintype "passive"))
      (node (ref "KEY_4") (pin "1") (pinfunction "ROW_1") (pintype "passive"))
      (node (ref "KEY_5") (pin "1") (pinfunction "ROW_1") (pintype "passive"))
      (node (ref "KEY_6") (pin "1") (pinfunction "ROW_1") (pintype "passive"))
      (node (ref "KEY_7") (pin "1") (pinfunction "ROW_1") (pintype "passive"))
      (node (ref "KEY_8") (pin "1") (pinfunction "ROW_1") (pintype "passive"))
      (node (ref "KEY_9") (pin "1") (pinfunction "ROW_1") (pintype "passive"))
      (node (ref "KEY_ADD") (pin "1") (pinfunction "ROW_1") (pintype "passive"))
      (node (ref "KEY_Backspace") (pin "1") (pinfunction "ROW_1") (pintype "passive"))
      (node (ref "KEY_Home") (pin "1") (pinfunction "ROW_1") (pintype "passive"))
      (node (ref "KEY_Insert") (pin "1") (pinfunction "ROW_1") (pintype "passive"))
      (node (ref "KEY_NumDIV") (pin "1") (pinfunction "ROW_1") (pintype "passive"))
      (node (ref "KEY_NumLock") (pin "1") (pinfunction "ROW_1") (pintype "passive"))
      (node (ref "KEY_NumMUL") (pin "1") (pinfunction "ROW_1") (pintype "passive"))
      (node (ref "KEY_NumSUB") (pin "1") (pinfunction "ROW_1") (pintype "passive"))
      (node (ref "KEY_PgUp") (pin "1") (pinfunction "ROW_1") (pintype "passive"))
      (node (ref "KEY_SUB") (pin "1") (pinfunction "ROW_1") (pintype "passive"))
      (node (ref "KEY_WAVE") (pin "1") (pinfunction "ROW_1") (pintype "passive"))
      (node (ref "R4") (pin "1") (pinfunction "1_1") (pintype "passive"))
      (node (ref "R5") (pin "2") (pinfunction "2_2") (pintype "passive"))
    )
    (net (code "35") (name "Net-(KEY_1-DI)") (class "Default")
      (node (ref "KEY_1") (pin "4") (pinfunction "DI_4") (pintype "passive"))
      (node (ref "KEY_2") (pin "3") (pinfunction "DO_3") (pintype "passive"))
    )
    (net (code "36") (name "Net-(KEY_1-DO)") (class "Default")
      (node (ref "KEY_1") (pin "3") (pinfunction "DO_3") (pintype "passive"))
      (node (ref "KEY_WAVE") (pin "4") (pinfunction "DI_4") (pintype "passive"))
    )
    (net (code "37") (name "Net-(KEY_2-DI)") (class "Default")
      (node (ref "KEY_2") (pin "4") (pinfunction "DI_4") (pintype "passive"))
      (node (ref "KEY_3") (pin "3") (pinfunction "DO_3") (pintype "passive"))
    )
    (net (code "38") (name "Net-(KEY_3-DI)") (class "Default")
      (node (ref "KEY_3") (pin "4") (pinfunction "DI_4") (pintype "passive"))
      (node (ref "KEY_4") (pin "3") (pinfunction "DO_3") (pintype "passive"))
    )
    (net (code "39") (name "Net-(KEY_4-DI)") (class "Default")
      (node (ref "KEY_4") (pin "4") (pinfunction "DI_4") (pintype "passive"))
      (node (ref "KEY_5") (pin "3") (pinfunction "DO_3") (pintype "passive"))
    )
    (net (code "40") (name "Net-(KEY_5-DI)") (class "Default")
      (node (ref "KEY_5") (pin "4") (pinfunction "DI_4") (pintype "passive"))
      (node (ref "KEY_6") (pin "3") (pinfunction "DO_3") (pintype "passive"))
    )
    (net (code "41") (name "Net-(KEY_6-DI)") (class "Default")
      (node (ref "KEY_6") (pin "4") (pinfunction "DI_4") (pintype "passive"))
      (node (ref "KEY_7") (pin "3") (pinfunction "DO_3") (pintype "passive"))
    )
    (net (code "42") (name "Net-(KEY_7-DI)") (class "Default")
      (node (ref "KEY_7") (pin "4") (pinfunction "DI_4") (pintype "passive"))
      (node (ref "KEY_8") (pin "3") (pinfunction "DO_3") (pintype "passive"))
    )
    (net (code "43") (name "Net-(KEY_8-DI)") (class "Default")
      (node (ref "KEY_8") (pin "4") (pinfunction "DI_4") (pintype "passive"))
      (node (ref "KEY_9") (pin "3") (pinfunction "DO_3") (pintype "passive"))
    )
    (net (code "44") (name "Net-(KEY_A-DI)") (class "Default")
      (node (ref "KEY_A") (pin "4") (pinfunction "DI_4") (pintype "passive"))
      (node (ref "KEY_S") (pin "3") (pinfunction "DO_3") (pintype "passive"))
    )
    (net (code "45") (name "Net-(KEY_A-DO)") (class "Default")
      (node (ref "KEY_A") (pin "3") (pinfunction "DO_3") (pintype "passive"))
      (node (ref "KEY_CapsLock") (pin "4") (pinfunction "DI_4") (pintype "passive"))
    )
    (net (code "46") (name "Net-(KEY_A-ROW)") (class "Default")
      (node (ref "KEY_A") (pin "1") (pinfunction "ROW_1") (pintype "passive"))
      (node (ref "KEY_CapsLock") (pin "1") (pinfunction "ROW_1") (pintype "passive"))
      (node (ref "KEY_Colon") (pin "1") (pinfunction "ROW_1") (pintype "passive"))
      (node (ref "KEY_D") (pin "1") (pinfunction "ROW_1") (pintype "passive"))
      (node (ref "KEY_Enter") (pin "1") (pinfunction "ROW_1") (pintype "passive"))
      (node (ref "KEY_F") (pin "1") (pinfunction "ROW_1") (pintype "passive"))
      (node (ref "KEY_G") (pin "1") (pinfunction "ROW_1") (pintype "passive"))
      (node (ref "KEY_H") (pin "1") (pinfunction "ROW_1") (pintype "passive"))
      (node (ref "KEY_J") (pin "1") (pinfunction "ROW_1") (pintype "passive"))
      (node (ref "KEY_K") (pin "1") (pinfunction "ROW_1") (pintype "passive"))
      (node (ref "KEY_L") (pin "1") (pinfunction "ROW_1") (pintype "passive"))
      (node (ref "KEY_Num4") (pin "1") (pinfunction "ROW_1") (pintype "passive"))
      (node (ref "KEY_Num5") (pin "1") (pinfunction "ROW_1") (pintype "passive"))
      (node (ref "KEY_Num6") (pin "1") (pinfunction "ROW_1") (pintype "passive"))
      (node (ref "KEY_Quotation") (pin "1") (pinfunction "ROW_1") (pintype "passive"))
      (node (ref "KEY_S") (pin "1") (pinfunction "ROW_1") (pintype "passive"))
      (node (ref "R8") (pin "1") (pinfunction "1_1") (pintype "passive"))
      (node (ref "R9") (pin "2") (pinfunction "2_2") (pintype "passive"))
    )
    (net (code "47") (name "Net-(KEY_ADD-DI)") (class "Default")
      (node (ref "KEY_ADD") (pin "4") (pinfunction "DI_4") (pintype "passive"))
      (node (ref "KEY_Backspace") (pin "3") (pinfunction "DO_3") (pintype "passive"))
    )
    (net (code "48") (name "Net-(KEY_ADD-DO)") (class "Default")
      (node (ref "KEY_ADD") (pin "3") (pinfunction "DO_3") (pintype "passive"))
      (node (ref "KEY_SUB") (pin "4") (pinfunction "DI_4") (pintype "passive"))
    )
    (net (code "49") (name "Net-(KEY_B-DI)") (class "Default")
      (node (ref "KEY_B") (pin "4") (pinfunction "DI_4") (pintype "passive"))
      (node (ref "KEY_N") (pin "3") (pinfunction "DO_3") (pintype "passive"))
    )
    (net (code "50") (name "Net-(KEY_B-DO)") (class "Default")
      (node (ref "KEY_B") (pin "3") (pinfunction "DO_3") (pintype "passive"))
      (node (ref "KEY_V") (pin "4") (pinfunction "DI_4") (pintype "passive"))
    )
    (net (code "51") (name "Net-(KEY_B-ROW)") (class "Default")
      (node (ref "KEY_B") (pin "1") (pinfunction "ROW_1") (pintype "passive"))
      (node (ref "KEY_C") (pin "1") (pinfunction "ROW_1") (pintype "passive"))
      (node (ref "KEY_Comma") (pin "1") (pinfunction "ROW_1") (pintype "passive"))
      (node (ref "KEY_FullStop") (pin "1") (pinfunction "ROW_1") (pintype "passive"))
      (node (ref "KEY_LShift") (pin "1") (pinfunction "ROW_1") (pintype "passive"))
      (node (ref "KEY_M") (pin "1") (pinfunction "ROW_1") (pintype "passive"))
      (node (ref "KEY_N") (pin "1") (pinfunction "ROW_1") (pintype "passive"))
      (node (ref "KEY_Num1") (pin "1") (pinfunction "ROW_1") (pintype "passive"))
      (node (ref "KEY_Num2") (pin "1") (pinfunction "ROW_1") (pintype "passive"))
      (node (ref "KEY_Num3") (pin "1") (pinfunction "ROW_1") (pintype "passive"))
      (node (ref "KEY_NumEnter") (pin "1") (pinfunction "ROW_1") (pintype "passive"))
      (node (ref "KEY_RShift") (pin "1") (pinfunction "ROW_1") (pintype "passive"))
      (node (ref "KEY_Slash") (pin "1") (pinfunction "ROW_1") (pintype "passive"))
      (node (ref "KEY_UP") (pin "1") (pinfunction "ROW_1") (pintype "passive"))
      (node (ref "KEY_V") (pin "1") (pinfunction "ROW_1") (pintype "passive"))
      (node (ref "KEY_X") (pin "1") (pinfunction "ROW_1") (pintype "passive"))
      (node (ref "KEY_Z") (pin "1") (pinfunction "ROW_1") (pintype "passive"))
      (node (ref "R10") (pin "1") (pinfunction "1_1") (pintype "passive"))
      (node (ref "R11") (pin "2") (pinfunction "2_2") (pintype "passive"))
    )
    (net (code "52") (name "Net-(KEY_Backslash-DI)") (class "Default")
      (node (ref "KEY_Backslash") (pin "4") (pinfunction "DI_4") (pintype "passive"))
      (node (ref "KEY_Delete") (pin "3") (pinfunction "DO_3") (pintype "passive"))
    )
    (net (code "53") (name "Net-(KEY_Backslash-DO)") (class "Default")
      (node (ref "KEY_Backslash") (pin "3") (pinfunction "DO_3") (pintype "passive"))
      (node (ref "KEY_BackwardSquareBracket") (pin "4") (pinfunction "DI_4") (pintype "passive"))
    )
    (net (code "54") (name "Net-(KEY_Backslash-ROW)") (class "Default")
      (node (ref "KEY_Backslash") (pin "1") (pinfunction "ROW_1") (pintype "passive"))
      (node (ref "KEY_BackwardSquareBracket") (pin "1") (pinfunction "ROW_1") (pintype "passive"))
      (node (ref "KEY_Delete") (pin "1") (pinfunction "ROW_1") (pintype "passive"))
      (node (ref "KEY_E") (pin "1") (pinfunction "ROW_1") (pintype "passive"))
      (node (ref "KEY_End") (pin "1") (pinfunction "ROW_1") (pintype "passive"))
      (node (ref "KEY_ForwardSquareBracket") (pin "1") (pinfunction "ROW_1") (pintype "passive"))
      (node (ref "KEY_I") (pin "1") (pinfunction "ROW_1") (pintype "passive"))
      (node (ref "KEY_Num7") (pin "1") (pinfunction "ROW_1") (pintype "passive"))
      (node (ref "KEY_Num8") (pin "1") (pinfunction "ROW_1") (pintype "passive"))
      (node (ref "KEY_Num9") (pin "1") (pinfunction "ROW_1") (pintype "passive"))
      (node (ref "KEY_NumADD") (pin "1") (pinfunction "ROW_1") (pintype "passive"))
      (node (ref "KEY_O") (pin "1") (pinfunction "ROW_1") (pintype "passive"))
      (node (ref "KEY_P") (pin "1") (pinfunction "ROW_1") (pintype "passive"))
      (node (ref "KEY_PgDn") (pin "1") (pinfunction "ROW_1") (pintype "passive"))
      (node (ref "KEY_Q") (pin "1") (pinfunction "ROW_1") (pintype "passive"))
      (node (ref "KEY_R") (pin "1") (pinfunction "ROW_1") (pintype "passive"))
      (node (ref "KEY_T") (pin "1") (pinfunction "ROW_1") (pintype "passive"))
      (node (ref "KEY_Tab") (pin "1") (pinfunction "ROW_1") (pintype "passive"))
      (node (ref "KEY_U") (pin "1") (pinfunction "ROW_1") (pintype "passive"))
      (node (ref "KEY_W") (pin "1") (pinfunction "ROW_1") (pintype "passive"))
      (node (ref "KEY_Y") (pin "1") (pinfunction "ROW_1") (pintype "passive"))
      (node (ref "R6") (pin "1") (pinfunction "1_1") (pintype "passive"))
      (node (ref "R7") (pin "2") (pinfunction "2_2") (pintype "passive"))
    )
    (net (code "55") (name "Net-(KEY_Backspace-DI)") (class "Default")
      (node (ref "KEY_Backspace") (pin "4") (pinfunction "DI_4") (pintype "passive"))
      (node (ref "KEY_Insert") (pin "3") (pinfunction "DO_3") (pintype "passive"))
    )
    (net (code "56") (name "Net-(KEY_BackwardSquareBracket-DO)") (class "Default")
      (node (ref "KEY_BackwardSquareBracket") (pin "3") (pinfunction "DO_3") (pintype "passive"))
      (node (ref "KEY_ForwardSquareBracket") (pin "4") (pinfunction "DI_4") (pintype "passive"))
    )
    (net (code "57") (name "Net-(KEY_C-DI)") (class "Default")
      (node (ref "KEY_C") (pin "4") (pinfunction "DI_4") (pintype "passive"))
      (node (ref "KEY_V") (pin "3") (pinfunction "DO_3") (pintype "passive"))
    )
    (net (code "58") (name "Net-(KEY_C-DO)") (class "Default")
      (node (ref "KEY_C") (pin "3") (pinfunction "DO_3") (pintype "passive"))
      (node (ref "KEY_X") (pin "4") (pinfunction "DI_4") (pintype "passive"))
    )
    (net (code "59") (name "Net-(KEY_CapsLock-DO)") (class "Default")
      (node (ref "KEY_CapsLock") (pin "3") (pinfunction "DO_3") (pintype "passive"))
      (node (ref "KEY_NumEnter") (pin "4") (pinfunction "DI_4") (pintype "passive"))
    )
    (net (code "60") (name "Net-(KEY_Colon-DI)") (class "Default")
      (node (ref "KEY_Colon") (pin "4") (pinfunction "DI_4") (pintype "passive"))
      (node (ref "KEY_Quotation") (pin "3") (pinfunction "DO_3") (pintype "passive"))
    )
    (net (code "61") (name "Net-(KEY_Colon-DO)") (class "Default")
      (node (ref "KEY_Colon") (pin "3") (pinfunction "DO_3") (pintype "passive"))
      (node (ref "KEY_L") (pin "4") (pinfunction "DI_4") (pintype "passive"))
    )
    (net (code "62") (name "Net-(KEY_Comma-DI)") (class "Default")
      (node (ref "KEY_Comma") (pin "4") (pinfunction "DI_4") (pintype "passive"))
      (node (ref "KEY_FullStop") (pin "3") (pinfunction "DO_3") (pintype "passive"))
    )
    (net (code "63") (name "Net-(KEY_Comma-DO)") (class "Default")
      (node (ref "KEY_Comma") (pin "3") (pinfunction "DO_3") (pintype "passive"))
      (node (ref "KEY_M") (pin "4") (pinfunction "DI_4") (pintype "passive"))
    )
    (net (code "64") (name "Net-(KEY_D-DI)") (class "Default")
      (node (ref "KEY_D") (pin "4") (pinfunction "DI_4") (pintype "passive"))
      (node (ref "KEY_F") (pin "3") (pinfunction "DO_3") (pintype "passive"))
    )
    (net (code "65") (name "Net-(KEY_D-DO)") (class "Default")
      (node (ref "KEY_D") (pin "3") (pinfunction "DO_3") (pintype "passive"))
      (node (ref "KEY_S") (pin "4") (pinfunction "DI_4") (pintype "passive"))
    )
    (net (code "66") (name "Net-(KEY_DOWN-DI)") (class "Default")
      (node (ref "KEY_DOWN") (pin "4") (pinfunction "DI_4") (pintype "passive"))
      (node (ref "KEY_RIGHT") (pin "3") (pinfunction "DO_3") (pintype "passive"))
    )
    (net (code "67") (name "Net-(KEY_DOWN-DO)") (class "Default")
      (node (ref "KEY_DOWN") (pin "3") (pinfunction "DO_3") (pintype "passive"))
      (node (ref "KEY_LEFT") (pin "4") (pinfunction "DI_4") (pintype "passive"))
    )
    (net (code "68") (name "Net-(KEY_DOWN-ROW)") (class "Default")
      (node (ref "KEY_DOWN") (pin "1") (pinfunction "ROW_1") (pintype "passive"))
      (node (ref "KEY_Fn") (pin "1") (pinfunction "ROW_1") (pintype "passive"))
      (node (ref "KEY_LAlt") (pin "1") (pinfunction "ROW_1") (pintype "passive"))
      (node (ref "KEY_LCtrl") (pin "1") (pinfunction "ROW_1") (pintype "passive"))
      (node (ref "KEY_LEFT") (pin "1") (pinfunction "ROW_1") (pintype "passive"))
      (node (ref "KEY_LWin") (pin "1") (pinfunction "ROW_1") (pintype "passive"))
      (node (ref "KEY_Num0") (pin "1") (pinfunction "ROW_1") (pintype "passive"))
      (node (ref "KEY_NumFullStop") (pin "1") (pinfunction "ROW_1") (pintype "passive"))
      (node (ref "KEY_RAlt") (pin "1") (pinfunction "ROW_1") (pintype "passive"))
      (node (ref "KEY_RCtrl") (pin "1") (pinfunction "ROW_1") (pintype "passive"))
      (node (ref "KEY_RIGHT") (pin "1") (pinfunction "ROW_1") (pintype "passive"))
      (node (ref "KEY_RWin") (pin "1") (pinfunction "ROW_1") (pintype "passive"))
      (node (ref "KEY_Space") (pin "1") (pinfunction "ROW_1") (pintype "passive"))
      (node (ref "R12") (pin "1") (pinfunction "1_1") (pintype "passive"))
      (node (ref "R13") (pin "2") (pinfunction "2_2") (pintype "passive"))
    )
    (net (code "69") (name "Net-(KEY_Delete-DI)") (class "Default")
      (node (ref "KEY_Delete") (pin "4") (pinfunction "DI_4") (pintype "passive"))
      (node (ref "KEY_End") (pin "3") (pinfunction "DO_3") (pintype "passive"))
    )
    (net (code "70") (name "Net-(KEY_E-DI)") (class "Default")
      (node (ref "KEY_E") (pin "4") (pinfunction "DI_4") (pintype "passive"))
      (node (ref "KEY_R") (pin "3") (pinfunction "DO_3") (pintype "passive"))
    )
    (net (code "71") (name "Net-(KEY_E-DO)") (class "Default")
      (node (ref "KEY_E") (pin "3") (pinfunction "DO_3") (pintype "passive"))
      (node (ref "KEY_W") (pin "4") (pinfunction "DI_4") (pintype "passive"))
    )
    (net (code "72") (name "Net-(KEY_ESC-DI)") (class "Default")
      (node (ref "KEY_ESC") (pin "4") (pinfunction "DI_4") (pintype "passive"))
      (node (ref "KEY_F1") (pin "3") (pinfunction "DO_3") (pintype "passive"))
    )
    (net (code "73") (name "Net-(KEY_ESC-DO)") (class "Default")
      (node (ref "KEY_ESC") (pin "3") (pinfunction "DO_3") (pintype "passive"))
      (node (ref "KEY_NumSUB") (pin "4") (pinfunction "DI_4") (pintype "passive"))
    )
    (net (code "74") (name "Net-(KEY_ESC-ROW)") (class "Default")
      (node (ref "KEY_ESC") (pin "1") (pinfunction "ROW_1") (pintype "passive"))
      (node (ref "KEY_F1") (pin "1") (pinfunction "ROW_1") (pintype "passive"))
      (node (ref "KEY_F10") (pin "1") (pinfunction "ROW_1") (pintype "passive"))
      (node (ref "KEY_F11") (pin "1") (pinfunction "ROW_1") (pintype "passive"))
      (node (ref "KEY_F12") (pin "1") (pinfunction "ROW_1") (pintype "passive"))
      (node (ref "KEY_F2") (pin "1") (pinfunction "ROW_1") (pintype "passive"))
      (node (ref "KEY_F3") (pin "1") (pinfunction "ROW_1") (pintype "passive"))
      (node (ref "KEY_F4") (pin "1") (pinfunction "ROW_1") (pintype "passive"))
      (node (ref "KEY_F5") (pin "1") (pinfunction "ROW_1") (pintype "passive"))
      (node (ref "KEY_F6") (pin "1") (pinfunction "ROW_1") (pintype "passive"))
      (node (ref "KEY_F7") (pin "1") (pinfunction "ROW_1") (pintype "passive"))
      (node (ref "KEY_F8") (pin "1") (pinfunction "ROW_1") (pintype "passive"))
      (node (ref "KEY_F9") (pin "1") (pinfunction "ROW_1") (pintype "passive"))
      (node (ref "KEY_Pause") (pin "1") (pinfunction "ROW_1") (pintype "passive"))
      (node (ref "KEY_PrtSc") (pin "1") (pinfunction "ROW_1") (pintype "passive"))
      (node (ref "KEY_ScrollLock") (pin "1") (pinfunction "ROW_1") (pintype "passive"))
      (node (ref "R2") (pin "1") (pinfunction "1_1") (pintype "passive"))
      (node (ref "R3") (pin "2") (pinfunction "2_2") (pintype "passive"))
    )
    (net (code "75") (name "Net-(KEY_End-DI)") (class "Default")
      (node (ref "KEY_End") (pin "4") (pinfunction "DI_4") (pintype "passive"))
      (node (ref "KEY_PgDn") (pin "3") (pinfunction "DO_3") (pintype "passive"))
    )
    (net (code "76") (name "Net-(KEY_Enter-DI)") (class "Default")
      (node (ref "KEY_Enter") (pin "4") (pinfunction "DI_4") (pintype "passive"))
      (node (ref "KEY_Num4") (pin "3") (pinfunction "DO_3") (pintype "passive"))
    )
    (net (code "77") (name "Net-(KEY_Enter-DO)") (class "Default")
      (node (ref "KEY_Enter") (pin "3") (pinfunction "DO_3") (pintype "passive"))
      (node (ref "KEY_Quotation") (pin "4") (pinfunction "DI_4") (pintype "passive"))
    )
    (net (code "78") (name "Net-(KEY_F-DI)") (class "Default")
      (node (ref "KEY_F") (pin "4") (pinfunction "DI_4") (pintype "passive"))
      (node (ref "KEY_G") (pin "3") (pinfunction "DO_3") (pintype "passive"))
    )
    (net (code "79") (name "Net-(KEY_F1-DI)") (class "Default")
      (node (ref "KEY_F1") (pin "4") (pinfunction "DI_4") (pintype "passive"))
      (node (ref "KEY_F2") (pin "3") (pinfunction "DO_3") (pintype "passive"))
    )
    (net (code "80") (name "Net-(KEY_F2-DI)") (class "Default")
      (node (ref "KEY_F2") (pin "4") (pinfunction "DI_4") (pintype "passive"))
      (node (ref "KEY_F3") (pin "3") (pinfunction "DO_3") (pintype "passive"))
    )
    (net (code "81") (name "Net-(KEY_F3-DI)") (class "Default")
      (node (ref "KEY_F3") (pin "4") (pinfunction "DI_4") (pintype "passive"))
      (node (ref "KEY_F4") (pin "3") (pinfunction "DO_3") (pintype "passive"))
    )
    (net (code "82") (name "Net-(KEY_F4-DI)") (class "Default")
      (node (ref "KEY_F4") (pin "4") (pinfunction "DI_4") (pintype "passive"))
      (node (ref "KEY_F5") (pin "3") (pinfunction "DO_3") (pintype "passive"))
    )
    (net (code "83") (name "Net-(KEY_F5-DI)") (class "Default")
      (node (ref "KEY_F5") (pin "4") (pinfunction "DI_4") (pintype "passive"))
      (node (ref "KEY_F6") (pin "3") (pinfunction "DO_3") (pintype "passive"))
    )
    (net (code "84") (name "Net-(KEY_F6-DI)") (class "Default")
      (node (ref "KEY_F6") (pin "4") (pinfunction "DI_4") (pintype "passive"))
      (node (ref "KEY_F7") (pin "3") (pinfunction "DO_3") (pintype "passive"))
    )
    (net (code "85") (name "Net-(KEY_F7-DI)") (class "Default")
      (node (ref "KEY_F7") (pin "4") (pinfunction "DI_4") (pintype "passive"))
      (node (ref "KEY_F8") (pin "3") (pinfunction "DO_3") (pintype "passive"))
    )
    (net (code "86") (name "Net-(KEY_F8-DI)") (class "Default")
      (node (ref "KEY_F8") (pin "4") (pinfunction "DI_4") (pintype "passive"))
      (node (ref "KEY_F9") (pin "3") (pinfunction "DO_3") (pintype "passive"))
    )
    (net (code "87") (name "Net-(KEY_F10-DI)") (class "Default")
      (node (ref "KEY_F10") (pin "4") (pinfunction "DI_4") (pintype "passive"))
      (node (ref "KEY_F11") (pin "3") (pinfunction "DO_3") (pintype "passive"))
    )
    (net (code "88") (name "Net-(KEY_F10-DO)") (class "Default")
      (node (ref "KEY_F10") (pin "3") (pinfunction "DO_3") (pintype "passive"))
      (node (ref "KEY_F9") (pin "4") (pinfunction "DI_4") (pintype "passive"))
    )
    (net (code "89") (name "Net-(KEY_F11-DI)") (class "Default")
      (node (ref "KEY_F11") (pin "4") (pinfunction "DI_4") (pintype "passive"))
      (node (ref "KEY_F12") (pin "3") (pinfunction "DO_3") (pintype "passive"))
    )
    (net (code "90") (name "Net-(KEY_Fn-DI)") (class "Default")
      (node (ref "KEY_Fn") (pin "4") (pinfunction "DI_4") (pintype "passive"))
      (node (ref "KEY_RCtrl") (pin "3") (pinfunction "DO_3") (pintype "passive"))
    )
    (net (code "91") (name "Net-(KEY_Fn-DO)") (class "Default")
      (node (ref "KEY_Fn") (pin "3") (pinfunction "DO_3") (pintype "passive"))
      (node (ref "KEY_RWin") (pin "4") (pinfunction "DI_4") (pintype "passive"))
    )
    (net (code "92") (name "Net-(KEY_ForwardSquareBracket-DO)") (class "Default")
      (node (ref "KEY_ForwardSquareBracket") (pin "3") (pinfunction "DO_3") (pintype "passive"))
      (node (ref "KEY_P") (pin "4") (pinfunction "DI_4") (pintype "passive"))
    )
    (net (code "93") (name "Net-(KEY_FullStop-DI)") (class "Default")
      (node (ref "KEY_FullStop") (pin "4") (pinfunction "DI_4") (pintype "passive"))
      (node (ref "KEY_Slash") (pin "3") (pinfunction "DO_3") (pintype "passive"))
    )
    (net (code "94") (name "Net-(KEY_G-DI)") (class "Default")
      (node (ref "KEY_G") (pin "4") (pinfunction "DI_4") (pintype "passive"))
      (node (ref "KEY_H") (pin "3") (pinfunction "DO_3") (pintype "passive"))
    )
    (net (code "95") (name "Net-(KEY_H-DI)") (class "Default")
      (node (ref "KEY_H") (pin "4") (pinfunction "DI_4") (pintype "passive"))
      (node (ref "KEY_J") (pin "3") (pinfunction "DO_3") (pintype "passive"))
    )
    (net (code "96") (name "Net-(KEY_Home-DI)") (class "Default")
      (node (ref "KEY_Home") (pin "4") (pinfunction "DI_4") (pintype "passive"))
      (node (ref "KEY_PgUp") (pin "3") (pinfunction "DO_3") (pintype "passive"))
    )
    (net (code "97") (name "Net-(KEY_Home-DO)") (class "Default")
      (node (ref "KEY_Home") (pin "3") (pinfunction "DO_3") (pintype "passive"))
      (node (ref "KEY_Insert") (pin "4") (pinfunction "DI_4") (pintype "passive"))
    )
    (net (code "98") (name "Net-(KEY_I-DI)") (class "Default")
      (node (ref "KEY_I") (pin "4") (pinfunction "DI_4") (pintype "passive"))
      (node (ref "KEY_O") (pin "3") (pinfunction "DO_3") (pintype "passive"))
    )
    (net (code "99") (name "Net-(KEY_I-DO)") (class "Default")
      (node (ref "KEY_I") (pin "3") (pinfunction "DO_3") (pintype "passive"))
      (node (ref "KEY_U") (pin "4") (pinfunction "DI_4") (pintype "passive"))
    )
    (net (code "100") (name "Net-(KEY_J-DI)") (class "Default")
      (node (ref "KEY_J") (pin "4") (pinfunction "DI_4") (pintype "passive"))
      (node (ref "KEY_K") (pin "3") (pinfunction "DO_3") (pintype "passive"))
    )
    (net (code "101") (name "Net-(KEY_K-DI)") (class "Default")
      (node (ref "KEY_K") (pin "4") (pinfunction "DI_4") (pintype "passive"))
      (node (ref "KEY_L") (pin "3") (pinfunction "DO_3") (pintype "passive"))
    )
    (net (code "102") (name "Net-(KEY_LAlt-DI)") (class "Default")
      (node (ref "KEY_LAlt") (pin "4") (pinfunction "DI_4") (pintype "passive"))
      (node (ref "KEY_Space") (pin "3") (pinfunction "DO_3") (pintype "passive"))
    )
    (net (code "103") (name "Net-(KEY_LAlt-DO)") (class "Default")
      (node (ref "KEY_LAlt") (pin "3") (pinfunction "DO_3") (pintype "passive"))
      (node (ref "KEY_LWin") (pin "4") (pinfunction "DI_4") (pintype "passive"))
    )
    (net (code "104") (name "Net-(KEY_LCtrl-DI)") (class "Default")
      (node (ref "KEY_LCtrl") (pin "4") (pinfunction "DI_4") (pintype "passive"))
      (node (ref "KEY_LWin") (pin "3") (pinfunction "DO_3") (pintype "passive"))
    )
    (net (code "105") (name "Net-(KEY_LCtrl-DO)") (class "Default")
      (node (ref "KEY_LCtrl") (pin "3") (pinfunction "DO_3") (pintype "passive"))
      (node (ref "R1") (pin "2") (pinfunction "2_2") (pintype "passive"))
    )
    (net (code "106") (name "Net-(KEY_LEFT-DO)") (class "Default")
      (node (ref "KEY_LEFT") (pin "3") (pinfunction "DO_3") (pintype "passive"))
      (node (ref "KEY_RCtrl") (pin "4") (pinfunction "DI_4") (pintype "passive"))
    )
    (net (code "107") (name "Net-(KEY_LShift-DI)") (class "Default")
      (node (ref "KEY_LShift") (pin "4") (pinfunction "DI_4") (pintype "passive"))
      (node (ref "KEY_Z") (pin "3") (pinfunction "DO_3") (pintype "passive"))
    )
    (net (code "108") (name "Net-(KEY_LShift-DO)") (class "Default")
      (node (ref "KEY_LShift") (pin "3") (pinfunction "DO_3") (pintype "passive"))
      (node (ref "KEY_NumFullStop") (pin "4") (pinfunction "DI_4") (pintype "passive"))
    )
    (net (code "109") (name "Net-(KEY_M-DO)") (class "Default")
      (node (ref "KEY_M") (pin "3") (pinfunction "DO_3") (pintype "passive"))
      (node (ref "KEY_N") (pin "4") (pinfunction "DI_4") (pintype "passive"))
    )
    (net (code "110") (name "Net-(KEY_Num0-DI)") (class "Default")
      (node (ref "KEY_Num0") (pin "4") (pinfunction "DI_4") (pintype "passive"))
      (node (ref "KEY_NumFullStop") (pin "3") (pinfunction "DO_3") (pintype "passive"))
    )
    (net (code "111") (name "Net-(KEY_Num0-DO)") (class "Default")
      (node (ref "KEY_Num0") (pin "3") (pinfunction "DO_3") (pintype "passive"))
      (node (ref "KEY_RIGHT") (pin "4") (pinfunction "DI_4") (pintype "passive"))
    )
    (net (code "112") (name "Net-(KEY_Num1-DI)") (class "Default")
      (node (ref "KEY_Num1") (pin "4") (pinfunction "DI_4") (pintype "passive"))
      (node (ref "KEY_Num2") (pin "3") (pinfunction "DO_3") (pintype "passive"))
    )
    (net (code "113") (name "Net-(KEY_Num1-DO)") (class "Default")
      (node (ref "KEY_Num1") (pin "3") (pinfunction "DO_3") (pintype "passive"))
      (node (ref "KEY_UP") (pin "4") (pinfunction "DI_4") (pintype "passive"))
    )
    (net (code "114") (name "Net-(KEY_Num2-DI)") (class "Default")
      (node (ref "KEY_Num2") (pin "4") (pinfunction "DI_4") (pintype "passive"))
      (node (ref "KEY_Num3") (pin "3") (pinfunction "DO_3") (pintype "passive"))
    )
    (net (code "115") (name "Net-(KEY_Num3-DI)") (class "Default")
      (node (ref "KEY_Num3") (pin "4") (pinfunction "DI_4") (pintype "passive"))
      (node (ref "KEY_NumEnter") (pin "3") (pinfunction "DO_3") (pintype "passive"))
    )
    (net (code "116") (name "Net-(KEY_Num4-DI)") (class "Default")
      (node (ref "KEY_Num4") (pin "4") (pinfunction "DI_4") (pintype "passive"))
      (node (ref "KEY_Num5") (pin "3") (pinfunction "DO_3") (pintype "passive"))
    )
    (net (code "117") (name "Net-(KEY_Num5-DI)") (class "Default")
      (node (ref "KEY_Num5") (pin "4") (pinfunction "DI_4") (pintype "passive"))
      (node (ref "KEY_Num6") (pin "3") (pinfunction "DO_3") (pintype "passive"))
    )
    (net (code "118") (name "Net-(KEY_Num6-DI)") (class "Default")
      (node (ref "KEY_Num6") (pin "4") (pinfunction "DI_4") (pintype "passive"))
      (node (ref "KEY_Tab") (pin "3") (pinfunction "DO_3") (pintype "passive"))
    )
    (net (code "119") (name "Net-(KEY_Num7-DI)") (class "Default")
      (node (ref "KEY_Num7") (pin "4") (pinfunction "DI_4") (pintype "passive"))
      (node (ref "KEY_Num8") (pin "3") (pinfunction "DO_3") (pintype "passive"))
    )
    (net (code "120") (name "Net-(KEY_Num7-DO)") (class "Default")
      (node (ref "KEY_Num7") (pin "3") (pinfunction "DO_3") (pintype "passive"))
      (node (ref "KEY_PgDn") (pin "4") (pinfunction "DI_4") (pintype "passive"))
    )
    (net (code "121") (name "Net-(KEY_Num8-DI)") (class "Default")
      (node (ref "KEY_Num8") (pin "4") (pinfunction "DI_4") (pintype "passive"))
      (node (ref "KEY_Num9") (pin "3") (pinfunction "DO_3") (pintype "passive"))
    )
    (net (code "122") (name "Net-(KEY_Num9-DI)") (class "Default")
      (node (ref "KEY_Num9") (pin "4") (pinfunction "DI_4") (pintype "passive"))
      (node (ref "KEY_NumADD") (pin "3") (pinfunction "DO_3") (pintype "passive"))
    )
    (net (code "123") (name "Net-(KEY_NumADD-DI)") (class "Default")
      (node (ref "KEY_NumADD") (pin "4") (pinfunction "DI_4") (pintype "passive"))
      (node (ref "KEY_WAVE") (pin "3") (pinfunction "DO_3") (pintype "passive"))
    )
    (net (code "124") (name "Net-(KEY_NumDIV-DI)") (class "Default")
      (node (ref "KEY_NumDIV") (pin "4") (pinfunction "DI_4") (pintype "passive"))
      (node (ref "KEY_NumMUL") (pin "3") (pinfunction "DO_3") (pintype "passive"))
    )
    (net (code "125") (name "Net-(KEY_NumDIV-DO)") (class "Default")
      (node (ref "KEY_NumDIV") (pin "3") (pinfunction "DO_3") (pintype "passive"))
      (node (ref "KEY_NumLock") (pin "4") (pinfunction "DI_4") (pintype "passive"))
    )
    (net (code "126") (name "Net-(KEY_NumLock-DO)") (class "Default")
      (node (ref "KEY_NumLock") (pin "3") (pinfunction "DO_3") (pintype "passive"))
      (node (ref "KEY_PgUp") (pin "4") (pinfunction "DI_4") (pintype "passive"))
    )
    (net (code "127") (name "Net-(KEY_NumMUL-DI)") (class "Default")
      (node (ref "KEY_NumMUL") (pin "4") (pinfunction "DI_4") (pintype "passive"))
      (node (ref "KEY_NumSUB") (pin "3") (pinfunction "DO_3") (pintype "passive"))
    )
    (net (code "128") (name "Net-(KEY_O-DI)") (class "Default")
      (node (ref "KEY_O") (pin "4") (pinfunction "DI_4") (pintype "passive"))
      (node (ref "KEY_P") (pin "3") (pinfunction "DO_3") (pintype "passive"))
    )
    (net (code "129") (name "Net-(KEY_Pause-DI)") (class "Default")
      (node (ref "KEY_Pause") (pin "4") (pinfunction "DI_4") (pintype "passive"))
      (node (ref "R0") (pin "1") (pinfunction "1_1") (pintype "passive"))
    )
    (net (code "130") (name "Net-(KEY_Pause-DO)") (class "Default")
      (node (ref "KEY_Pause") (pin "3") (pinfunction "DO_3") (pintype "passive"))
      (node (ref "KEY_ScrollLock") (pin "4") (pinfunction "DI_4") (pintype "passive"))
    )
    (net (code "131") (name "Net-(KEY_PrtSc-DI)") (class "Default")
      (node (ref "KEY_PrtSc") (pin "4") (pinfunction "DI_4") (pintype "passive"))
      (node (ref "KEY_ScrollLock") (pin "3") (pinfunction "DO_3") (pintype "passive"))
    )
    (net (code "132") (name "Net-(KEY_Q-DI)") (class "Default")
      (node (ref "KEY_Q") (pin "4") (pinfunction "DI_4") (pintype "passive"))
      (node (ref "KEY_W") (pin "3") (pinfunction "DO_3") (pintype "passive"))
    )
    (net (code "133") (name "Net-(KEY_Q-DO)") (class "Default")
      (node (ref "KEY_Q") (pin "3") (pinfunction "DO_3") (pintype "passive"))
      (node (ref "KEY_Tab") (pin "4") (pinfunction "DI_4") (pintype "passive"))
    )
    (net (code "134") (name "Net-(KEY_R-DI)") (class "Default")
      (node (ref "KEY_R") (pin "4") (pinfunction "DI_4") (pintype "passive"))
      (node (ref "KEY_T") (pin "3") (pinfunction "DO_3") (pintype "passive"))
    )
    (net (code "135") (name "Net-(KEY_RAlt-DI)") (class "Default")
      (node (ref "KEY_RAlt") (pin "4") (pinfunction "DI_4") (pintype "passive"))
      (node (ref "KEY_RWin") (pin "3") (pinfunction "DO_3") (pintype "passive"))
    )
    (net (code "136") (name "Net-(KEY_RAlt-DO)") (class "Default")
      (node (ref "KEY_RAlt") (pin "3") (pinfunction "DO_3") (pintype "passive"))
      (node (ref "KEY_Space") (pin "4") (pinfunction "DI_4") (pintype "passive"))
    )
    (net (code "137") (name "Net-(KEY_RShift-DI)") (class "Default")
      (node (ref "KEY_RShift") (pin "4") (pinfunction "DI_4") (pintype "passive"))
      (node (ref "KEY_UP") (pin "3") (pinfunction "DO_3") (pintype "passive"))
    )
    (net (code "138") (name "Net-(KEY_RShift-DO)") (class "Default")
      (node (ref "KEY_RShift") (pin "3") (pinfunction "DO_3") (pintype "passive"))
      (node (ref "KEY_Slash") (pin "4") (pinfunction "DI_4") (pintype "passive"))
    )
    (net (code "139") (name "Net-(KEY_T-DI)") (class "Default")
      (node (ref "KEY_T") (pin "4") (pinfunction "DI_4") (pintype "passive"))
      (node (ref "KEY_Y") (pin "3") (pinfunction "DO_3") (pintype "passive"))
    )
    (net (code "140") (name "Net-(KEY_U-DO)") (class "Default")
      (node (ref "KEY_U") (pin "3") (pinfunction "DO_3") (pintype "passive"))
      (node (ref "KEY_Y") (pin "4") (pinfunction "DI_4") (pintype "passive"))
    )
    (net (code "141") (name "Net-(KEY_X-DO)") (class "Default")
      (node (ref "KEY_X") (pin "3") (pinfunction "DO_3") (pintype "passive"))
      (node (ref "KEY_Z") (pin "4") (pinfunction "DI_4") (pintype "passive"))
    )
    (net (code "142") (name "unconnected-(J1-Pad29)") (class "Default")
      (node (ref "J1") (pin "29") (pinfunction "29_29") (pintype "passive"))
    )
    (net (code "143") (name "unconnected-(J1-Pad30)") (class "Default")
      (node (ref "J1") (pin "30") (pinfunction "30_30") (pintype "passive"))
    )
    (net (code "144") (name "unconnected-(KEY_F12-DI-Pad4)") (class "Default")
      (node (ref "KEY_F12") (pin "4") (pinfunction "DI_4") (pintype "passive"))
    )
    (net (code "145") (name "unconnected-(KEY_PrtSc-DO-Pad3)") (class "Default")
      (node (ref "KEY_PrtSc") (pin "3") (pinfunction "DO_3") (pintype "passive"))
    )
    (net (code "146") (name "unconnected-(R1-Pad1)") (class "Default")
      (node (ref "R1") (pin "1") (pinfunction "1_1") (pintype "passive"))
    )
  )
)
